# TinyNES_Main_Board.net
KiCad netlist of a schematic drawn in EAGLE
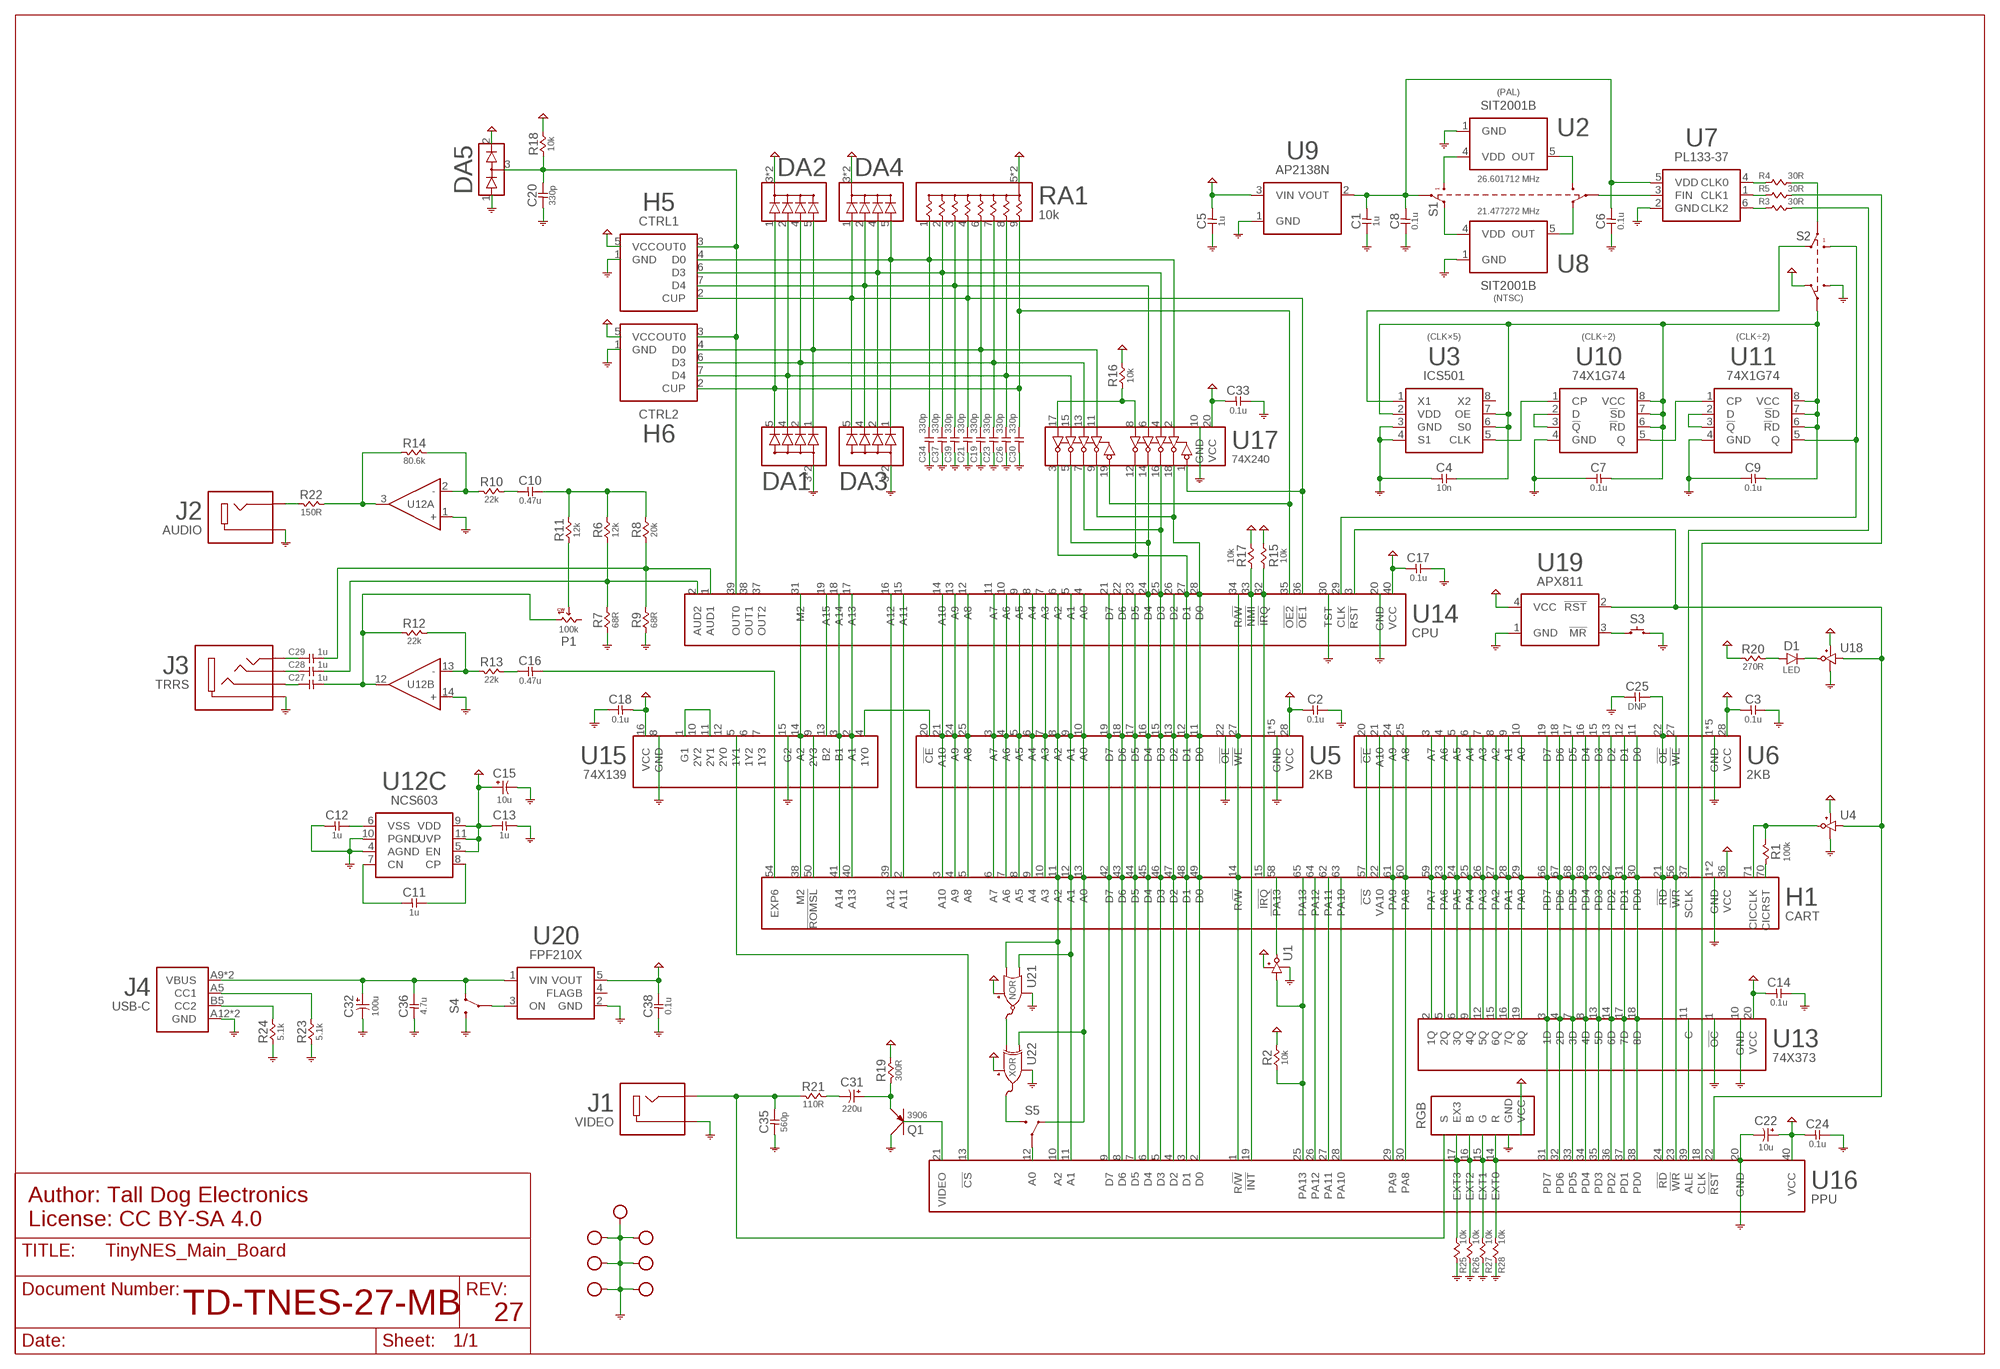
[diagram p0: schematic, sheet 1]

(export (version "E")
  (design (tool "Eeschema 10.0.6"))
  (components
    (comp (ref "C1")
      (value "1u")
      (footprint "eagle-import:0805-NP")
      (libsource (lib "eagle-import") (part "CAP-NP-0805"))
    )
    (comp (ref "C2")
      (value "0.1u")
      (footprint "eagle-import:0805-NP")
      (libsource (lib "eagle-import") (part "CAP-NP-0805"))
    )
    (comp (ref "C3")
      (value "0.1u")
      (footprint "eagle-import:0805-NP")
      (libsource (lib "eagle-import") (part "CAP-NP-0805"))
    )
    (comp (ref "C4")
      (value "10n")
      (footprint "eagle-import:0805-NP")
      (libsource (lib "eagle-import") (part "CAP-NP-0805"))
    )
    (comp (ref "C5")
      (value "1u")
      (footprint "eagle-import:0805-NP")
      (libsource (lib "eagle-import") (part "CAP-NP-0805"))
    )
    (comp (ref "C6")
      (value "0.1u")
      (footprint "eagle-import:0805-NP")
      (libsource (lib "eagle-import") (part "CAP-NP-0805"))
    )
    (comp (ref "C7")
      (value "0.1u")
      (footprint "eagle-import:0805-NP")
      (libsource (lib "eagle-import") (part "CAP-NP-0805"))
    )
    (comp (ref "C8")
      (value "0.1u")
      (footprint "eagle-import:0805-NP")
      (libsource (lib "eagle-import") (part "CAP-NP-0805"))
    )
    (comp (ref "C9")
      (value "0.1u")
      (footprint "eagle-import:0805-NP")
      (libsource (lib "eagle-import") (part "CAP-NP-0805"))
    )
    (comp (ref "C10")
      (value "0.47u")
      (footprint "eagle-import:1206-NP")
      (libsource (lib "eagle-import") (part "CAP-NP-1206"))
    )
    (comp (ref "C11")
      (value "1u")
      (footprint "eagle-import:0805-NP")
      (libsource (lib "eagle-import") (part "CAP-NP-0805"))
    )
    (comp (ref "C12")
      (value "1u")
      (footprint "eagle-import:0805-NP")
      (libsource (lib "eagle-import") (part "CAP-NP-0805"))
    )
    (comp (ref "C13")
      (value "1u")
      (footprint "eagle-import:0805-NP")
      (libsource (lib "eagle-import") (part "CAP-NP-0805"))
    )
    (comp (ref "C14")
      (value "0.1u")
      (footprint "eagle-import:0805-NP")
      (libsource (lib "eagle-import") (part "CAP-NP-0805"))
    )
    (comp (ref "C15")
      (value "10u")
      (footprint "eagle-import:ECAP-B")
      (libsource (lib "eagle-import") (part "CAP-P-B"))
    )
    (comp (ref "C16")
      (value "0.47u")
      (footprint "eagle-import:1206-NP")
      (libsource (lib "eagle-import") (part "CAP-NP-1206"))
    )
    (comp (ref "C17")
      (value "0.1u")
      (footprint "eagle-import:0805-NP")
      (libsource (lib "eagle-import") (part "CAP-NP-0805"))
    )
    (comp (ref "C18")
      (value "0.1u")
      (footprint "eagle-import:0805-NP")
      (libsource (lib "eagle-import") (part "CAP-NP-0805"))
    )
    (comp (ref "C19")
      (value "330p")
      (footprint "eagle-import:0805-NP")
      (libsource (lib "eagle-import") (part "CAP-NP-0805"))
    )
    (comp (ref "C20")
      (value "330p")
      (footprint "eagle-import:0805-NP")
      (libsource (lib "eagle-import") (part "CAP-NP-0805"))
    )
    (comp (ref "C21")
      (value "330p")
      (footprint "eagle-import:0805-NP")
      (libsource (lib "eagle-import") (part "CAP-NP-0805"))
    )
    (comp (ref "C22")
      (value "10u")
      (footprint "eagle-import:1206-P")
      (libsource (lib "eagle-import") (part "CAP-P-1206"))
    )
    (comp (ref "C23")
      (value "330p")
      (footprint "eagle-import:0805-NP")
      (libsource (lib "eagle-import") (part "CAP-NP-0805"))
    )
    (comp (ref "C24")
      (value "0.1u")
      (footprint "eagle-import:0805-NP")
      (libsource (lib "eagle-import") (part "CAP-NP-0805"))
    )
    (comp (ref "C25")
      (value "DNP")
      (footprint "eagle-import:0805-NP")
      (libsource (lib "eagle-import") (part "CAP-NP-0805"))
    )
    (comp (ref "C26")
      (value "330p")
      (footprint "eagle-import:0805-NP")
      (libsource (lib "eagle-import") (part "CAP-NP-0805"))
    )
    (comp (ref "C27")
      (value "1u")
      (footprint "eagle-import:1210-NP")
      (libsource (lib "eagle-import") (part "CAP-NP-1210"))
    )
    (comp (ref "C28")
      (value "1u")
      (footprint "eagle-import:1210-NP")
      (libsource (lib "eagle-import") (part "CAP-NP-1210"))
    )
    (comp (ref "C29")
      (value "1u")
      (footprint "eagle-import:1210-NP")
      (libsource (lib "eagle-import") (part "CAP-NP-1210"))
    )
    (comp (ref "C30")
      (value "330p")
      (footprint "eagle-import:0805-NP")
      (libsource (lib "eagle-import") (part "CAP-NP-0805"))
    )
    (comp (ref "C31")
      (value "220u")
      (footprint "eagle-import:ECAP-E")
      (libsource (lib "eagle-import") (part "CAP-P-E"))
    )
    (comp (ref "C32")
      (value "100u")
      (footprint "eagle-import:ECAP-D")
      (libsource (lib "eagle-import") (part "CAP-P-D"))
    )
    (comp (ref "C33")
      (value "0.1u")
      (footprint "eagle-import:0805-NP")
      (libsource (lib "eagle-import") (part "CAP-NP-0805"))
    )
    (comp (ref "C34")
      (value "330p")
      (footprint "eagle-import:0805-NP")
      (libsource (lib "eagle-import") (part "CAP-NP-0805"))
    )
    (comp (ref "C35")
      (value "560p")
      (footprint "eagle-import:0805-NP")
      (libsource (lib "eagle-import") (part "CAP-NP-0805"))
    )
    (comp (ref "C36")
      (value "4.7u")
      (footprint "eagle-import:0805-NP")
      (libsource (lib "eagle-import") (part "CAP-NP-0805"))
    )
    (comp (ref "C37")
      (value "330p")
      (footprint "eagle-import:0805-NP")
      (libsource (lib "eagle-import") (part "CAP-NP-0805"))
    )
    (comp (ref "C38")
      (value "0.1u")
      (footprint "eagle-import:0805-NP")
      (libsource (lib "eagle-import") (part "CAP-NP-0805"))
    )
    (comp (ref "C39")
      (value "330p")
      (footprint "eagle-import:0805-NP")
      (libsource (lib "eagle-import") (part "CAP-NP-0805"))
    )
    (comp (ref "D1")
      (value "LED")
      (footprint "eagle-import:LED-5MM")
      (libsource (lib "eagle-import") (part "DIODE-LED-5MM"))
    )
    (comp (ref "DA1")
      (value "DA4-CA-SOT-363")
      (footprint "eagle-import:SOT-363-NP")
      (libsource (lib "eagle-import") (part "DA4-CA-SOT-363"))
    )
    (comp (ref "DA2")
      (value "DA4-CK-SOT-363")
      (footprint "eagle-import:SOT-363-NP")
      (libsource (lib "eagle-import") (part "DA4-CK-SOT-363"))
    )
    (comp (ref "DA3")
      (value "DA4-CA-SOT-363")
      (footprint "eagle-import:SOT-363-NP")
      (libsource (lib "eagle-import") (part "DA4-CA-SOT-363"))
    )
    (comp (ref "DA4")
      (value "DA4-CK-SOT-363")
      (footprint "eagle-import:SOT-363-NP")
      (libsource (lib "eagle-import") (part "DA4-CK-SOT-363"))
    )
    (comp (ref "DA5")
      (value "DA2-S")
      (footprint "eagle-import:SOT-23-3")
      (libsource (lib "eagle-import") (part "DA2-S"))
    )
    (comp (ref "H1")
      (value "CART")
      (footprint "eagle-import:CART-72-2.50-CONN-VERT")
      (libsource (lib "eagle-import") (part "CART-72-CONN-VERT"))
    )
    (comp (ref "H5")
      (value "CTRL1")
      (footprint "eagle-import:JST-PH-7")
      (libsource (lib "eagle-import") (part "CTRL"))
    )
    (comp (ref "H6")
      (value "CTRL2")
      (footprint "eagle-import:JST-PH-7")
      (libsource (lib "eagle-import") (part "CTRL"))
    )
    (comp (ref "HOLE1")
      (value "HOLE-M2.5")
      (footprint "eagle-import:HOLE-M2.5")
      (libsource (lib "eagle-import") (part "HOLE-M2.5"))
    )
    (comp (ref "HOLE2")
      (value "HOLE-M2.5")
      (footprint "eagle-import:HOLE-M2.5")
      (libsource (lib "eagle-import") (part "HOLE-M2.5"))
    )
    (comp (ref "HOLE3")
      (value "HOLE-M2.5")
      (footprint "eagle-import:HOLE-M2.5")
      (libsource (lib "eagle-import") (part "HOLE-M2.5"))
    )
    (comp (ref "HOLE4")
      (value "HOLE-M2.5")
      (footprint "eagle-import:HOLE-M2.5")
      (libsource (lib "eagle-import") (part "HOLE-M2.5"))
    )
    (comp (ref "HOLE5")
      (value "HOLE-M2.5")
      (footprint "eagle-import:HOLE-M2.5")
      (libsource (lib "eagle-import") (part "HOLE-M2.5"))
    )
    (comp (ref "HOLE6")
      (value "HOLE-M2.5")
      (footprint "eagle-import:HOLE-M2.5")
      (libsource (lib "eagle-import") (part "HOLE-M2.5"))
    )
    (comp (ref "HOLE7")
      (value "HOLE-M2.5")
      (footprint "eagle-import:HOLE-M2.5")
      (libsource (lib "eagle-import") (part "HOLE-M2.5"))
    )
    (comp (ref "J1")
      (value "VIDEO")
      (footprint "eagle-import:RCJ")
      (libsource (lib "eagle-import") (part "JACK"))
    )
    (comp (ref "J2")
      (value "AUDIO")
      (footprint "eagle-import:RCJ")
      (libsource (lib "eagle-import") (part "JACK"))
    )
    (comp (ref "J3")
      (value "TRRS")
      (footprint "eagle-import:SJ-43514")
      (libsource (lib "eagle-import") (part "TRRS-SJ-43514"))
    )
    (comp (ref "J4")
      (value "USB-C")
      (footprint "eagle-import:USB4125")
      (libsource (lib "eagle-import") (part "USB-C-POWER"))
    )
    (comp (ref "P1")
      (value "100k")
      (footprint "eagle-import:POT-3361")
      (libsource (lib "eagle-import") (part "POT"))
    )
    (comp (ref "Q1")
      (value "3906")
      (footprint "eagle-import:SOT-23-3")
      (libsource (lib "eagle-import") (part "PNP"))
    )
    (comp (ref "R1")
      (value "100k")
      (footprint "eagle-import:0805-NP")
      (libsource (lib "eagle-import") (part "RESISTOR-0805"))
    )
    (comp (ref "R2")
      (value "10k")
      (footprint "eagle-import:0805-NP")
      (libsource (lib "eagle-import") (part "RESISTOR-0805"))
    )
    (comp (ref "R3")
      (value "30R")
      (footprint "eagle-import:0805-NP")
      (libsource (lib "eagle-import") (part "RESISTOR-0805"))
    )
    (comp (ref "R4")
      (value "30R")
      (footprint "eagle-import:0805-NP")
      (libsource (lib "eagle-import") (part "RESISTOR-0805"))
    )
    (comp (ref "R5")
      (value "30R")
      (footprint "eagle-import:0805-NP")
      (libsource (lib "eagle-import") (part "RESISTOR-0805"))
    )
    (comp (ref "R6")
      (value "12k")
      (footprint "eagle-import:0805-NP")
      (libsource (lib "eagle-import") (part "RESISTOR-0805"))
    )
    (comp (ref "R7")
      (value "68R")
      (footprint "eagle-import:0805-NP")
      (libsource (lib "eagle-import") (part "RESISTOR-0805"))
    )
    (comp (ref "R8")
      (value "20k")
      (footprint "eagle-import:0805-NP")
      (libsource (lib "eagle-import") (part "RESISTOR-0805"))
    )
    (comp (ref "R9")
      (value "68R")
      (footprint "eagle-import:0805-NP")
      (libsource (lib "eagle-import") (part "RESISTOR-0805"))
    )
    (comp (ref "R10")
      (value "22k")
      (footprint "eagle-import:0805-NP")
      (libsource (lib "eagle-import") (part "RESISTOR-0805"))
    )
    (comp (ref "R11")
      (value "12k")
      (footprint "eagle-import:0805-NP")
      (libsource (lib "eagle-import") (part "RESISTOR-0805"))
    )
    (comp (ref "R12")
      (value "22k")
      (footprint "eagle-import:0805-NP")
      (libsource (lib "eagle-import") (part "RESISTOR-0805"))
    )
    (comp (ref "R13")
      (value "22k")
      (footprint "eagle-import:0805-NP")
      (libsource (lib "eagle-import") (part "RESISTOR-0805"))
    )
    (comp (ref "R14")
      (value "80.6k")
      (footprint "eagle-import:0805-NP")
      (libsource (lib "eagle-import") (part "RESISTOR-0805"))
    )
    (comp (ref "R15")
      (value "10k")
      (footprint "eagle-import:0805-NP")
      (libsource (lib "eagle-import") (part "RESISTOR-0805"))
    )
    (comp (ref "R16")
      (value "10k")
      (footprint "eagle-import:0805-NP")
      (libsource (lib "eagle-import") (part "RESISTOR-0805"))
    )
    (comp (ref "R17")
      (value "10k")
      (footprint "eagle-import:0805-NP")
      (libsource (lib "eagle-import") (part "RESISTOR-0805"))
    )
    (comp (ref "R18")
      (value "10k")
      (footprint "eagle-import:0805-NP")
      (libsource (lib "eagle-import") (part "RESISTOR-0805"))
    )
    (comp (ref "R19")
      (value "300R")
      (footprint "eagle-import:0805-NP")
      (libsource (lib "eagle-import") (part "RESISTOR-0805"))
    )
    (comp (ref "R20")
      (value "270R")
      (footprint "eagle-import:0805-NP")
      (libsource (lib "eagle-import") (part "RESISTOR-0805"))
    )
    (comp (ref "R21")
      (value "110R")
      (footprint "eagle-import:0805-NP")
      (libsource (lib "eagle-import") (part "RESISTOR-0805"))
    )
    (comp (ref "R22")
      (value "150R")
      (footprint "eagle-import:0805-NP")
      (libsource (lib "eagle-import") (part "RESISTOR-0805"))
    )
    (comp (ref "R23")
      (value "5.1k")
      (footprint "eagle-import:0805-NP")
      (libsource (lib "eagle-import") (part "RESISTOR-0805"))
    )
    (comp (ref "R24")
      (value "5.1k")
      (footprint "eagle-import:0805-NP")
      (libsource (lib "eagle-import") (part "RESISTOR-0805"))
    )
    (comp (ref "R25")
      (value "10k")
      (footprint "eagle-import:0603-NP")
      (libsource (lib "eagle-import") (part "RESISTOR-0603"))
    )
    (comp (ref "R26")
      (value "10k")
      (footprint "eagle-import:0603-NP")
      (libsource (lib "eagle-import") (part "RESISTOR-0603"))
    )
    (comp (ref "R27")
      (value "10k")
      (footprint "eagle-import:0603-NP")
      (libsource (lib "eagle-import") (part "RESISTOR-0603"))
    )
    (comp (ref "R28")
      (value "10k")
      (footprint "eagle-import:0603-NP")
      (libsource (lib "eagle-import") (part "RESISTOR-0603"))
    )
    (comp (ref "RA1")
      (value "10k")
      (footprint "eagle-import:EXBA10P")
      (libsource (lib "eagle-import") (part "RA8"))
    )
    (comp (ref "RGB")
      (value "RGB-TOP")
      (footprint "eagle-import:RGB-TOP")
      (libsource (lib "eagle-import") (part "RGB-TOP"))
    )
    (comp (ref "S1")
      (value "DPDT-LONG")
      (footprint "eagle-import:JS202011J")
      (libsource (lib "eagle-import") (part "DPDT-LONG"))
    )
    (comp (ref "S2")
      (value "DPDT")
      (footprint "eagle-import:JS202011J")
      (libsource (lib "eagle-import") (part "DPDT"))
    )
    (comp (ref "S3")
      (value "SWITCH")
      (footprint "eagle-import:TL1105")
      (libsource (lib "eagle-import") (part "SWITCH"))
    )
    (comp (ref "S4")
      (value "SPDT-EG1213")
      (footprint "eagle-import:EG1213")
      (libsource (lib "eagle-import") (part "SPDT-EG1213"))
    )
    (comp (ref "S5")
      (value "SPDT-CUS-12TB")
      (footprint "eagle-import:CUS-12TB")
      (libsource (lib "eagle-import") (part "SPDT-CUS-12TB"))
    )
    (comp (ref "U1")
      (value "BUFFER")
      (footprint "eagle-import:SOT-23-5")
      (libsource (lib "eagle-import") (part "BUFFER"))
    )
    (comp (ref "U2")
      (value "SIT2001B")
      (footprint "eagle-import:SOT-23-5")
      (libsource (lib "eagle-import") (part "SIT2001B"))
    )
    (comp (ref "U3")
      (value "ICS501")
      (footprint "eagle-import:SOIC-8")
      (libsource (lib "eagle-import") (part "ICS501"))
    )
    (comp (ref "U4")
      (value "BUFFER")
      (footprint "eagle-import:SOT-23-5")
      (libsource (lib "eagle-import") (part "BUFFER"))
    )
    (comp (ref "U5")
      (value "2KB")
      (footprint "eagle-import:SOIC-28")
      (libsource (lib "eagle-import") (part "2KB"))
    )
    (comp (ref "U6")
      (value "2KB")
      (footprint "eagle-import:SOIC-28")
      (libsource (lib "eagle-import") (part "2KB"))
    )
    (comp (ref "U7")
      (value "PL133-37")
      (footprint "eagle-import:SOT-23-6")
      (libsource (lib "eagle-import") (part "PL133-37"))
    )
    (comp (ref "U8")
      (value "SIT2001B")
      (footprint "eagle-import:SOT-23-5")
      (libsource (lib "eagle-import") (part "SIT2001B"))
    )
    (comp (ref "U9")
      (value "AP2138N")
      (footprint "eagle-import:SOT-23-3")
      (libsource (lib "eagle-import") (part "AP2138N"))
    )
    (comp (ref "U10")
      (value "74X1G74")
      (footprint "eagle-import:TSSOP-8")
      (libsource (lib "eagle-import") (part "74X1G74"))
    )
    (comp (ref "U11")
      (value "74X1G74")
      (footprint "eagle-import:TSSOP-8")
      (libsource (lib "eagle-import") (part "74X1G74"))
    )
    (comp (ref "U12")
      (value "NCS603")
      (footprint "eagle-import:TSSOP-14")
      (libsource (lib "eagle-import") (part "NCS603"))
    )
    (comp (ref "U13")
      (value "74X373")
      (footprint "eagle-import:SOIC-20")
      (libsource (lib "eagle-import") (part "74X373"))
    )
    (comp (ref "U14")
      (value "CPU")
      (footprint "eagle-import:DIP-40")
      (libsource (lib "eagle-import") (part "CPU"))
    )
    (comp (ref "U15")
      (value "74X139")
      (footprint "eagle-import:SOIC-16")
      (libsource (lib "eagle-import") (part "74X139"))
    )
    (comp (ref "U16")
      (value "PPU")
      (footprint "eagle-import:DIP-40")
      (libsource (lib "eagle-import") (part "PPU"))
    )
    (comp (ref "U17")
      (value "74X240")
      (footprint "eagle-import:SOIC-20")
      (libsource (lib "eagle-import") (part "74X240"))
    )
    (comp (ref "U18")
      (value "BUFFER")
      (footprint "eagle-import:SOT-23-5")
      (libsource (lib "eagle-import") (part "BUFFER"))
    )
    (comp (ref "U19")
      (value "APX811")
      (footprint "eagle-import:SOT-143")
      (libsource (lib "eagle-import") (part "APX811"))
    )
    (comp (ref "U20")
      (value "FPF210X")
      (footprint "eagle-import:SOT-23-5")
      (libsource (lib "eagle-import") (part "FPF210X"))
    )
    (comp (ref "U21")
      (value "NOR")
      (footprint "eagle-import:SOT-23-5")
      (libsource (lib "eagle-import") (part "NOR"))
    )
    (comp (ref "U22")
      (value "XOR")
      (footprint "eagle-import:SOT-23-5")
      (libsource (lib "eagle-import") (part "XOR"))
    )
  )
  (nets
    (net (code "1") (name "GND") (class "Default")
      (node (ref "C1") (pin "2") (pinfunction "2_2") (pintype "bidirectional"))
      (node (ref "C12") (pin "1") (pinfunction "1_1") (pintype "bidirectional"))
      (node (ref "C13") (pin "1") (pinfunction "1_1") (pintype "bidirectional"))
      (node (ref "C14") (pin "2") (pinfunction "2_2") (pintype "bidirectional"))
      (node (ref "C15") (pin "C") (pinfunction "C_C") (pintype "bidirectional"))
      (node (ref "C17") (pin "2") (pinfunction "2_2") (pintype "bidirectional"))
      (node (ref "C18") (pin "2") (pinfunction "2_2") (pintype "bidirectional"))
      (node (ref "C19") (pin "1") (pinfunction "1_1") (pintype "bidirectional"))
      (node (ref "C2") (pin "2") (pinfunction "2_2") (pintype "bidirectional"))
      (node (ref "C20") (pin "1") (pinfunction "1_1") (pintype "bidirectional"))
      (node (ref "C21") (pin "1") (pinfunction "1_1") (pintype "bidirectional"))
      (node (ref "C22") (pin "N") (pinfunction "C_N") (pintype "bidirectional"))
      (node (ref "C23") (pin "1") (pinfunction "1_1") (pintype "bidirectional"))
      (node (ref "C24") (pin "2") (pinfunction "2_2") (pintype "bidirectional"))
      (node (ref "C25") (pin "1") (pinfunction "1_1") (pintype "bidirectional"))
      (node (ref "C26") (pin "1") (pinfunction "1_1") (pintype "bidirectional"))
      (node (ref "C3") (pin "2") (pinfunction "2_2") (pintype "bidirectional"))
      (node (ref "C30") (pin "1") (pinfunction "1_1") (pintype "bidirectional"))
      (node (ref "C32") (pin "C") (pinfunction "C_C") (pintype "bidirectional"))
      (node (ref "C33") (pin "2") (pinfunction "2_2") (pintype "bidirectional"))
      (node (ref "C34") (pin "1") (pinfunction "1_1") (pintype "bidirectional"))
      (node (ref "C35") (pin "1") (pinfunction "1_1") (pintype "bidirectional"))
      (node (ref "C36") (pin "1") (pinfunction "1_1") (pintype "bidirectional"))
      (node (ref "C37") (pin "1") (pinfunction "1_1") (pintype "bidirectional"))
      (node (ref "C38") (pin "1") (pinfunction "1_1") (pintype "bidirectional"))
      (node (ref "C39") (pin "1") (pinfunction "1_1") (pintype "bidirectional"))
      (node (ref "C4") (pin "1") (pinfunction "1_1") (pintype "bidirectional"))
      (node (ref "C5") (pin "2") (pinfunction "2_2") (pintype "bidirectional"))
      (node (ref "C6") (pin "2") (pinfunction "2_2") (pintype "bidirectional"))
      (node (ref "C7") (pin "2") (pinfunction "2_2") (pintype "bidirectional"))
      (node (ref "C8") (pin "2") (pinfunction "2_2") (pintype "bidirectional"))
      (node (ref "C9") (pin "2") (pinfunction "2_2") (pintype "bidirectional"))
      (node (ref "DA1") (pin "3") (pinfunction "COM_3") (pintype "bidirectional"))
      (node (ref "DA1") (pin "6") (pinfunction "COM_6") (pintype "bidirectional"))
      (node (ref "DA3") (pin "3") (pinfunction "COM_3") (pintype "bidirectional"))
      (node (ref "DA3") (pin "6") (pinfunction "COM_6") (pintype "bidirectional"))
      (node (ref "DA5") (pin "1") (pinfunction "A_1") (pintype "bidirectional"))
      (node (ref "H1") (pin "1") (pinfunction "GND_1") (pintype "bidirectional"))
      (node (ref "H1") (pin "72") (pinfunction "GND_72") (pintype "bidirectional"))
      (node (ref "H5") (pin "1") (pinfunction "GND_1") (pintype "bidirectional"))
      (node (ref "H6") (pin "1") (pinfunction "GND_1") (pintype "bidirectional"))
      (node (ref "HOLE1") (pin "P$1") (pinfunction "P$1_P$1") (pintype "bidirectional"))
      (node (ref "HOLE1") (pin "P$13") (pinfunction "P$1_P$13") (pintype "bidirectional"))
      (node (ref "HOLE1") (pin "P$14") (pinfunction "P$1_P$14") (pintype "bidirectional"))
      (node (ref "HOLE1") (pin "P$15") (pinfunction "P$1_P$15") (pintype "bidirectional"))
      (node (ref "HOLE1") (pin "P$16") (pinfunction "P$1_P$16") (pintype "bidirectional"))
      (node (ref "HOLE1") (pin "P$6") (pinfunction "P$1_P$6") (pintype "bidirectional"))
      (node (ref "HOLE1") (pin "P$7") (pinfunction "P$1_P$7") (pintype "bidirectional"))
      (node (ref "HOLE1") (pin "P$8") (pinfunction "P$1_P$8") (pintype "bidirectional"))
      (node (ref "HOLE1") (pin "P$9") (pinfunction "P$1_P$9") (pintype "bidirectional"))
      (node (ref "HOLE2") (pin "P$1") (pinfunction "P$1_P$1") (pintype "bidirectional"))
      (node (ref "HOLE2") (pin "P$13") (pinfunction "P$1_P$13") (pintype "bidirectional"))
      (node (ref "HOLE2") (pin "P$14") (pinfunction "P$1_P$14") (pintype "bidirectional"))
      (node (ref "HOLE2") (pin "P$15") (pinfunction "P$1_P$15") (pintype "bidirectional"))
      (node (ref "HOLE2") (pin "P$16") (pinfunction "P$1_P$16") (pintype "bidirectional"))
      (node (ref "HOLE2") (pin "P$6") (pinfunction "P$1_P$6") (pintype "bidirectional"))
      (node (ref "HOLE2") (pin "P$7") (pinfunction "P$1_P$7") (pintype "bidirectional"))
      (node (ref "HOLE2") (pin "P$8") (pinfunction "P$1_P$8") (pintype "bidirectional"))
      (node (ref "HOLE2") (pin "P$9") (pinfunction "P$1_P$9") (pintype "bidirectional"))
      (node (ref "HOLE3") (pin "P$1") (pinfunction "P$1_P$1") (pintype "bidirectional"))
      (node (ref "HOLE3") (pin "P$13") (pinfunction "P$1_P$13") (pintype "bidirectional"))
      (node (ref "HOLE3") (pin "P$14") (pinfunction "P$1_P$14") (pintype "bidirectional"))
      (node (ref "HOLE3") (pin "P$15") (pinfunction "P$1_P$15") (pintype "bidirectional"))
      (node (ref "HOLE3") (pin "P$16") (pinfunction "P$1_P$16") (pintype "bidirectional"))
      (node (ref "HOLE3") (pin "P$6") (pinfunction "P$1_P$6") (pintype "bidirectional"))
      (node (ref "HOLE3") (pin "P$7") (pinfunction "P$1_P$7") (pintype "bidirectional"))
      (node (ref "HOLE3") (pin "P$8") (pinfunction "P$1_P$8") (pintype "bidirectional"))
      (node (ref "HOLE3") (pin "P$9") (pinfunction "P$1_P$9") (pintype "bidirectional"))
      (node (ref "HOLE4") (pin "P$1") (pinfunction "P$1_P$1") (pintype "bidirectional"))
      (node (ref "HOLE4") (pin "P$13") (pinfunction "P$1_P$13") (pintype "bidirectional"))
      (node (ref "HOLE4") (pin "P$14") (pinfunction "P$1_P$14") (pintype "bidirectional"))
      (node (ref "HOLE4") (pin "P$15") (pinfunction "P$1_P$15") (pintype "bidirectional"))
      (node (ref "HOLE4") (pin "P$16") (pinfunction "P$1_P$16") (pintype "bidirectional"))
      (node (ref "HOLE4") (pin "P$6") (pinfunction "P$1_P$6") (pintype "bidirectional"))
      (node (ref "HOLE4") (pin "P$7") (pinfunction "P$1_P$7") (pintype "bidirectional"))
      (node (ref "HOLE4") (pin "P$8") (pinfunction "P$1_P$8") (pintype "bidirectional"))
      (node (ref "HOLE4") (pin "P$9") (pinfunction "P$1_P$9") (pintype "bidirectional"))
      (node (ref "HOLE5") (pin "P$1") (pinfunction "P$1_P$1") (pintype "bidirectional"))
      (node (ref "HOLE5") (pin "P$13") (pinfunction "P$1_P$13") (pintype "bidirectional"))
      (node (ref "HOLE5") (pin "P$14") (pinfunction "P$1_P$14") (pintype "bidirectional"))
      (node (ref "HOLE5") (pin "P$15") (pinfunction "P$1_P$15") (pintype "bidirectional"))
      (node (ref "HOLE5") (pin "P$16") (pinfunction "P$1_P$16") (pintype "bidirectional"))
      (node (ref "HOLE5") (pin "P$6") (pinfunction "P$1_P$6") (pintype "bidirectional"))
      (node (ref "HOLE5") (pin "P$7") (pinfunction "P$1_P$7") (pintype "bidirectional"))
      (node (ref "HOLE5") (pin "P$8") (pinfunction "P$1_P$8") (pintype "bidirectional"))
      (node (ref "HOLE5") (pin "P$9") (pinfunction "P$1_P$9") (pintype "bidirectional"))
      (node (ref "HOLE6") (pin "P$1") (pinfunction "P$1_P$1") (pintype "bidirectional"))
      (node (ref "HOLE6") (pin "P$13") (pinfunction "P$1_P$13") (pintype "bidirectional"))
      (node (ref "HOLE6") (pin "P$14") (pinfunction "P$1_P$14") (pintype "bidirectional"))
      (node (ref "HOLE6") (pin "P$15") (pinfunction "P$1_P$15") (pintype "bidirectional"))
      (node (ref "HOLE6") (pin "P$16") (pinfunction "P$1_P$16") (pintype "bidirectional"))
      (node (ref "HOLE6") (pin "P$6") (pinfunction "P$1_P$6") (pintype "bidirectional"))
      (node (ref "HOLE6") (pin "P$7") (pinfunction "P$1_P$7") (pintype "bidirectional"))
      (node (ref "HOLE6") (pin "P$8") (pinfunction "P$1_P$8") (pintype "bidirectional"))
      (node (ref "HOLE6") (pin "P$9") (pinfunction "P$1_P$9") (pintype "bidirectional"))
      (node (ref "HOLE7") (pin "P$1") (pinfunction "P$1_P$1") (pintype "bidirectional"))
      (node (ref "HOLE7") (pin "P$13") (pinfunction "P$1_P$13") (pintype "bidirectional"))
      (node (ref "HOLE7") (pin "P$14") (pinfunction "P$1_P$14") (pintype "bidirectional"))
      (node (ref "HOLE7") (pin "P$15") (pinfunction "P$1_P$15") (pintype "bidirectional"))
      (node (ref "HOLE7") (pin "P$16") (pinfunction "P$1_P$16") (pintype "bidirectional"))
      (node (ref "HOLE7") (pin "P$6") (pinfunction "P$1_P$6") (pintype "bidirectional"))
      (node (ref "HOLE7") (pin "P$7") (pinfunction "P$1_P$7") (pintype "bidirectional"))
      (node (ref "HOLE7") (pin "P$8") (pinfunction "P$1_P$8") (pintype "bidirectional"))
      (node (ref "HOLE7") (pin "P$9") (pinfunction "P$1_P$9") (pintype "bidirectional"))
      (node (ref "J1") (pin "1B") (pinfunction "S_1B") (pintype "bidirectional"))
      (node (ref "J1") (pin "1T") (pinfunction "S_1T") (pintype "bidirectional"))
      (node (ref "J2") (pin "1B") (pinfunction "S_1B") (pintype "bidirectional"))
      (node (ref "J2") (pin "1T") (pinfunction "S_1T") (pintype "bidirectional"))
      (node (ref "J3") (pin "1") (pinfunction "S_1") (pintype "bidirectional"))
      (node (ref "J4") (pin "A12") (pinfunction "GND_A12") (pintype "bidirectional"))
      (node (ref "J4") (pin "B12") (pinfunction "GND_B12") (pintype "bidirectional"))
      (node (ref "Q1") (pin "3") (pinfunction "C_3") (pintype "bidirectional"))
      (node (ref "R23") (pin "1") (pinfunction "1_1") (pintype "bidirectional"))
      (node (ref "R24") (pin "1") (pinfunction "1_1") (pintype "bidirectional"))
      (node (ref "R25") (pin "1") (pinfunction "1_1") (pintype "bidirectional"))
      (node (ref "R26") (pin "1") (pinfunction "1_1") (pintype "bidirectional"))
      (node (ref "R27") (pin "1") (pinfunction "1_1") (pintype "bidirectional"))
      (node (ref "R28") (pin "1") (pinfunction "1_1") (pintype "bidirectional"))
      (node (ref "R7") (pin "1") (pinfunction "1_1") (pintype "bidirectional"))
      (node (ref "R9") (pin "1") (pinfunction "1_1") (pintype "bidirectional"))
      (node (ref "RGB") (pin "GND") (pinfunction "GND_GND") (pintype "bidirectional"))
      (node (ref "S2") (pin "AA") (pinfunction "4_AA") (pintype "bidirectional"))
      (node (ref "S3") (pin "2") (pinfunction "2_2") (pintype "bidirectional"))
      (node (ref "S4") (pin "3") (pinfunction "3_3") (pintype "bidirectional"))
      (node (ref "U1") (pin "1") (pinfunction "GND_1") (pintype "bidirectional"))
      (node (ref "U1") (pin "3") (pinfunction "GND_3") (pintype "bidirectional"))
      (node (ref "U10") (pin "4") (pinfunction "GND_4") (pintype "bidirectional"))
      (node (ref "U11") (pin "4") (pinfunction "GND_4") (pintype "bidirectional"))
      (node (ref "U12") (pin "1") (pinfunction "+_1") (pintype "input"))
      (node (ref "U12") (pin "10") (pinfunction "PGND_10") (pintype "bidirectional"))
      (node (ref "U12") (pin "14") (pinfunction "+_14") (pintype "input"))
      (node (ref "U12") (pin "4") (pinfunction "AGND_4") (pintype "bidirectional"))
      (node (ref "U13") (pin "1") (pinfunction "~{OC}_1") (pintype "bidirectional"))
      (node (ref "U13") (pin "10") (pinfunction "GND_10") (pintype "bidirectional"))
      (node (ref "U14") (pin "20") (pinfunction "GND_20") (pintype "bidirectional"))
      (node (ref "U14") (pin "30") (pinfunction "TST_30") (pintype "bidirectional"))
      (node (ref "U15") (pin "15") (pinfunction "G2_15") (pintype "bidirectional"))
      (node (ref "U15") (pin "8") (pinfunction "GND_8") (pintype "bidirectional"))
      (node (ref "U16") (pin "20") (pinfunction "GND_20") (pintype "bidirectional"))
      (node (ref "U17") (pin "10") (pinfunction "GND_10") (pintype "bidirectional"))
      (node (ref "U18") (pin "1") (pinfunction "GND_1") (pintype "bidirectional"))
      (node (ref "U18") (pin "3") (pinfunction "GND_3") (pintype "bidirectional"))
      (node (ref "U19") (pin "1") (pinfunction "GND_1") (pintype "bidirectional"))
      (node (ref "U2") (pin "1") (pinfunction "GND_1") (pintype "bidirectional"))
      (node (ref "U20") (pin "2") (pinfunction "GND_2") (pintype "bidirectional"))
      (node (ref "U21") (pin "3") (pinfunction "GND_3") (pintype "power_in"))
      (node (ref "U22") (pin "3") (pinfunction "GND_3") (pintype "power_in"))
      (node (ref "U3") (pin "3") (pinfunction "GND_3") (pintype "bidirectional"))
      (node (ref "U3") (pin "4") (pinfunction "S1_4") (pintype "bidirectional"))
      (node (ref "U4") (pin "1") (pinfunction "GND_1") (pintype "bidirectional"))
      (node (ref "U4") (pin "3") (pinfunction "GND_3") (pintype "bidirectional"))
      (node (ref "U5") (pin "1") (pinfunction "GND_1") (pintype "bidirectional"))
      (node (ref "U5") (pin "14") (pinfunction "GND_14") (pintype "bidirectional"))
      (node (ref "U5") (pin "2") (pinfunction "GND_2") (pintype "bidirectional"))
      (node (ref "U5") (pin "22") (pinfunction "~{OE}_22") (pintype "bidirectional"))
      (node (ref "U5") (pin "23") (pinfunction "GND_23") (pintype "bidirectional"))
      (node (ref "U5") (pin "26") (pinfunction "GND_26") (pintype "bidirectional"))
      (node (ref "U6") (pin "1") (pinfunction "GND_1") (pintype "bidirectional"))
      (node (ref "U6") (pin "14") (pinfunction "GND_14") (pintype "bidirectional"))
      (node (ref "U6") (pin "2") (pinfunction "GND_2") (pintype "bidirectional"))
      (node (ref "U6") (pin "23") (pinfunction "GND_23") (pintype "bidirectional"))
      (node (ref "U6") (pin "26") (pinfunction "GND_26") (pintype "bidirectional"))
      (node (ref "U7") (pin "2") (pinfunction "GND_2") (pintype "bidirectional"))
      (node (ref "U8") (pin "1") (pinfunction "GND_1") (pintype "bidirectional"))
      (node (ref "U9") (pin "1") (pinfunction "GND_1") (pintype "bidirectional"))
    )
    (net (code "2") (name "Net-(C10-Pad1)") (class "Default")
      (node (ref "C10") (pin "1") (pinfunction "1_1") (pintype "bidirectional"))
      (node (ref "R10") (pin "1") (pinfunction "1_1") (pintype "bidirectional"))
    )
    (net (code "3") (name "Net-(C10-Pad2)") (class "Default")
      (node (ref "C10") (pin "2") (pinfunction "2_2") (pintype "bidirectional"))
      (node (ref "R11") (pin "2") (pinfunction "2_2") (pintype "bidirectional"))
      (node (ref "R6") (pin "2") (pinfunction "2_2") (pintype "bidirectional"))
      (node (ref "R8") (pin "2") (pinfunction "2_2") (pintype "bidirectional"))
    )
    (net (code "4") (name "Net-(C16-Pad2)") (class "Default")
      (node (ref "C16") (pin "2") (pinfunction "2_2") (pintype "bidirectional"))
      (node (ref "R13") (pin "1") (pinfunction "1_1") (pintype "bidirectional"))
    )
    (net (code "5") (name "Net-(C31-PadC)") (class "Default")
      (node (ref "C31") (pin "C") (pinfunction "C_C") (pintype "bidirectional"))
      (node (ref "R21") (pin "1") (pinfunction "1_1") (pintype "bidirectional"))
    )
    (net (code "6") (name "Net-(C35-Pad2)") (class "Default")
      (node (ref "C35") (pin "2") (pinfunction "2_2") (pintype "bidirectional"))
      (node (ref "J1") (pin "2B") (pinfunction "T_2B") (pintype "bidirectional"))
      (node (ref "J1") (pin "2T") (pinfunction "T_2T") (pintype "bidirectional"))
      (node (ref "R21") (pin "2") (pinfunction "2_2") (pintype "bidirectional"))
      (node (ref "RGB") (pin "S") (pinfunction "S_S") (pintype "bidirectional"))
    )
    (net (code "7") (name "Net-(D1-C)") (class "Default")
      (node (ref "D1") (pin "K") (pinfunction "C_K") (pintype "bidirectional"))
      (node (ref "U18") (pin "4") (pinfunction "Y_4") (pintype "bidirectional"))
    )
    (net (code "8") (name "Net-(D1-PadA)") (class "Default")
      (node (ref "D1") (pin "A") (pinfunction "A_A") (pintype "bidirectional"))
      (node (ref "R20") (pin "1") (pinfunction "1_1") (pintype "bidirectional"))
    )
    (net (code "9") (name "Net-(DA1-3)") (class "Default")
      (node (ref "C26") (pin "2") (pinfunction "2_2") (pintype "bidirectional"))
      (node (ref "DA1") (pin "4") (pinfunction "3_4") (pintype "bidirectional"))
      (node (ref "DA2") (pin "2") (pinfunction "2_2") (pintype "bidirectional"))
      (node (ref "H6") (pin "7") (pinfunction "D4_7") (pintype "bidirectional"))
      (node (ref "RA1") (pin "8") (pinfunction "7_8") (pintype "bidirectional"))
      (node (ref "U17") (pin "15") (pinfunction "2A3_15") (pintype "bidirectional"))
    )
    (net (code "10") (name "Net-(DA1-4)") (class "Default")
      (node (ref "C30") (pin "2") (pinfunction "2_2") (pintype "bidirectional"))
      (node (ref "DA1") (pin "5") (pinfunction "4_5") (pintype "bidirectional"))
      (node (ref "DA2") (pin "1") (pinfunction "1_1") (pintype "bidirectional"))
      (node (ref "H6") (pin "2") (pinfunction "CUP_2") (pintype "bidirectional"))
      (node (ref "RA1") (pin "9") (pinfunction "8_9") (pintype "bidirectional"))
      (node (ref "U14") (pin "35") (pinfunction "~{OE2}_35") (pintype "bidirectional"))
      (node (ref "U17") (pin "19") (pinfunction "2~{OE}_19") (pintype "bidirectional"))
    )
    (net (code "11") (name "Net-(DA2-3)") (class "Default")
      (node (ref "C23") (pin "2") (pinfunction "2_2") (pintype "bidirectional"))
      (node (ref "DA1") (pin "2") (pinfunction "2_2") (pintype "bidirectional"))
      (node (ref "DA2") (pin "4") (pinfunction "3_4") (pintype "bidirectional"))
      (node (ref "H6") (pin "6") (pinfunction "D3_6") (pintype "bidirectional"))
      (node (ref "RA1") (pin "7") (pinfunction "6_7") (pintype "bidirectional"))
      (node (ref "U17") (pin "13") (pinfunction "2A2_13") (pintype "bidirectional"))
    )
    (net (code "12") (name "Net-(DA2-4)") (class "Default")
      (node (ref "C19") (pin "2") (pinfunction "2_2") (pintype "bidirectional"))
      (node (ref "DA1") (pin "1") (pinfunction "1_1") (pintype "bidirectional"))
      (node (ref "DA2") (pin "5") (pinfunction "4_5") (pintype "bidirectional"))
      (node (ref "H6") (pin "4") (pinfunction "D0_4") (pintype "bidirectional"))
      (node (ref "RA1") (pin "6") (pinfunction "5_6") (pintype "bidirectional"))
      (node (ref "U17") (pin "11") (pinfunction "2A1_11") (pintype "bidirectional"))
    )
    (net (code "13") (name "Net-(DA3-3)") (class "Default")
      (node (ref "C39") (pin "2") (pinfunction "2_2") (pintype "bidirectional"))
      (node (ref "DA3") (pin "4") (pinfunction "3_4") (pintype "bidirectional"))
      (node (ref "DA4") (pin "2") (pinfunction "2_2") (pintype "bidirectional"))
      (node (ref "H5") (pin "7") (pinfunction "D4_7") (pintype "bidirectional"))
      (node (ref "RA1") (pin "3") (pinfunction "3_3") (pintype "bidirectional"))
      (node (ref "U17") (pin "6") (pinfunction "1A3_6") (pintype "bidirectional"))
    )
    (net (code "14") (name "Net-(DA3-4)") (class "Default")
      (node (ref "C21") (pin "2") (pinfunction "2_2") (pintype "bidirectional"))
      (node (ref "DA3") (pin "5") (pinfunction "4_5") (pintype "bidirectional"))
      (node (ref "DA4") (pin "1") (pinfunction "1_1") (pintype "bidirectional"))
      (node (ref "H5") (pin "2") (pinfunction "CUP_2") (pintype "bidirectional"))
      (node (ref "RA1") (pin "4") (pinfunction "4_4") (pintype "bidirectional"))
      (node (ref "U14") (pin "36") (pinfunction "~{OE1}_36") (pintype "bidirectional"))
      (node (ref "U17") (pin "1") (pinfunction "1~{OE}_1") (pintype "bidirectional"))
    )
    (net (code "15") (name "Net-(DA4-3)") (class "Default")
      (node (ref "C37") (pin "2") (pinfunction "2_2") (pintype "bidirectional"))
      (node (ref "DA3") (pin "2") (pinfunction "2_2") (pintype "bidirectional"))
      (node (ref "DA4") (pin "4") (pinfunction "3_4") (pintype "bidirectional"))
      (node (ref "H5") (pin "6") (pinfunction "D3_6") (pintype "bidirectional"))
      (node (ref "RA1") (pin "2") (pinfunction "2_2") (pintype "bidirectional"))
      (node (ref "U17") (pin "4") (pinfunction "1A2_4") (pintype "bidirectional"))
    )
    (net (code "16") (name "Net-(DA4-4)") (class "Default")
      (node (ref "C34") (pin "2") (pinfunction "2_2") (pintype "bidirectional"))
      (node (ref "DA3") (pin "1") (pinfunction "1_1") (pintype "bidirectional"))
      (node (ref "DA4") (pin "5") (pinfunction "4_5") (pintype "bidirectional"))
      (node (ref "H5") (pin "4") (pinfunction "D0_4") (pintype "bidirectional"))
      (node (ref "RA1") (pin "1") (pinfunction "1_1") (pintype "bidirectional"))
      (node (ref "U17") (pin "2") (pinfunction "1A1_2") (pintype "bidirectional"))
    )
    (net (code "17") (name "Net-(DA5-COM)") (class "Default")
      (node (ref "C20") (pin "2") (pinfunction "2_2") (pintype "bidirectional"))
      (node (ref "DA5") (pin "3") (pinfunction "COM_3") (pintype "bidirectional"))
      (node (ref "H5") (pin "3") (pinfunction "OUT0_3") (pintype "bidirectional"))
      (node (ref "H6") (pin "3") (pinfunction "OUT0_3") (pintype "bidirectional"))
      (node (ref "R18") (pin "1") (pinfunction "1_1") (pintype "bidirectional"))
      (node (ref "U14") (pin "39") (pinfunction "OUT0_39") (pintype "bidirectional"))
    )
    (net (code "18") (name "Net-(H1-A0)") (class "Default")
      (node (ref "H1") (pin "13") (pinfunction "A0_13") (pintype "bidirectional"))
      (node (ref "S5") (pin "1") (pinfunction "1_1") (pintype "bidirectional"))
      (node (ref "U14") (pin "4") (pinfunction "A0_4") (pintype "bidirectional"))
      (node (ref "U22") (pin "1") (pinfunction "B_1") (pintype "input"))
      (node (ref "U5") (pin "10") (pinfunction "A0_10") (pintype "bidirectional"))
    )
    (net (code "19") (name "Net-(H1-A1)") (class "Default")
      (node (ref "H1") (pin "12") (pinfunction "A1_12") (pintype "bidirectional"))
      (node (ref "U14") (pin "5") (pinfunction "A1_5") (pintype "bidirectional"))
      (node (ref "U16") (pin "11") (pinfunction "A1_11") (pintype "bidirectional"))
      (node (ref "U21") (pin "1") (pinfunction "B_1") (pintype "input"))
      (node (ref "U5") (pin "9") (pinfunction "A1_9") (pintype "bidirectional"))
    )
    (net (code "20") (name "Net-(H1-A2)") (class "Default")
      (node (ref "H1") (pin "11") (pinfunction "A2_11") (pintype "bidirectional"))
      (node (ref "U14") (pin "6") (pinfunction "A2_6") (pintype "bidirectional"))
      (node (ref "U16") (pin "10") (pinfunction "A2_10") (pintype "bidirectional"))
      (node (ref "U21") (pin "2") (pinfunction "A_2") (pintype "input"))
      (node (ref "U5") (pin "8") (pinfunction "A2_8") (pintype "bidirectional"))
    )
    (net (code "21") (name "Net-(H1-A3)") (class "Default")
      (node (ref "H1") (pin "10") (pinfunction "A3_10") (pintype "bidirectional"))
      (node (ref "U14") (pin "7") (pinfunction "A3_7") (pintype "bidirectional"))
      (node (ref "U5") (pin "7") (pinfunction "A3_7") (pintype "bidirectional"))
    )
    (net (code "22") (name "Net-(H1-A4)") (class "Default")
      (node (ref "H1") (pin "9") (pinfunction "A4_9") (pintype "bidirectional"))
      (node (ref "U14") (pin "8") (pinfunction "A4_8") (pintype "bidirectional"))
      (node (ref "U5") (pin "6") (pinfunction "A4_6") (pintype "bidirectional"))
    )
    (net (code "23") (name "Net-(H1-A5)") (class "Default")
      (node (ref "H1") (pin "8") (pinfunction "A5_8") (pintype "bidirectional"))
      (node (ref "U14") (pin "9") (pinfunction "A5_9") (pintype "bidirectional"))
      (node (ref "U5") (pin "5") (pinfunction "A5_5") (pintype "bidirectional"))
    )
    (net (code "24") (name "Net-(H1-A6)") (class "Default")
      (node (ref "H1") (pin "7") (pinfunction "A6_7") (pintype "bidirectional"))
      (node (ref "U14") (pin "10") (pinfunction "A6_10") (pintype "bidirectional"))
      (node (ref "U5") (pin "4") (pinfunction "A6_4") (pintype "bidirectional"))
    )
    (net (code "25") (name "Net-(H1-A7)") (class "Default")
      (node (ref "H1") (pin "6") (pinfunction "A7_6") (pintype "bidirectional"))
      (node (ref "U14") (pin "11") (pinfunction "A7_11") (pintype "bidirectional"))
      (node (ref "U5") (pin "3") (pinfunction "A7_3") (pintype "bidirectional"))
    )
    (net (code "26") (name "Net-(H1-A8)") (class "Default")
      (node (ref "H1") (pin "5") (pinfunction "A8_5") (pintype "bidirectional"))
      (node (ref "U14") (pin "12") (pinfunction "A8_12") (pintype "bidirectional"))
      (node (ref "U5") (pin "25") (pinfunction "A8_25") (pintype "bidirectional"))
    )
    (net (code "27") (name "Net-(H1-A9)") (class "Default")
      (node (ref "H1") (pin "4") (pinfunction "A9_4") (pintype "bidirectional"))
      (node (ref "U14") (pin "13") (pinfunction "A9_13") (pintype "bidirectional"))
      (node (ref "U5") (pin "24") (pinfunction "A9_24") (pintype "bidirectional"))
    )
    (net (code "28") (name "Net-(H1-A10)") (class "Default")
      (node (ref "H1") (pin "3") (pinfunction "A10_3") (pintype "bidirectional"))
      (node (ref "U14") (pin "14") (pinfunction "A10_14") (pintype "bidirectional"))
      (node (ref "U5") (pin "21") (pinfunction "A10_21") (pintype "bidirectional"))
    )
    (net (code "29") (name "Net-(H1-A11)") (class "Default")
      (node (ref "H1") (pin "2") (pinfunction "A11_2") (pintype "bidirectional"))
      (node (ref "U14") (pin "15") (pinfunction "A11_15") (pintype "bidirectional"))
    )
    (net (code "30") (name "Net-(H1-A12)") (class "Default")
      (node (ref "H1") (pin "39") (pinfunction "A12_39") (pintype "bidirectional"))
      (node (ref "U14") (pin "16") (pinfunction "A12_16") (pintype "bidirectional"))
    )
    (net (code "31") (name "Net-(H1-A13)") (class "Default")
      (node (ref "H1") (pin "40") (pinfunction "A13_40") (pintype "bidirectional"))
      (node (ref "U14") (pin "17") (pinfunction "A13_17") (pintype "bidirectional"))
      (node (ref "U15") (pin "2") (pinfunction "A1_2") (pintype "bidirectional"))
    )
    (net (code "32") (name "Net-(H1-A14)") (class "Default")
      (node (ref "H1") (pin "41") (pinfunction "A14_41") (pintype "bidirectional"))
      (node (ref "U14") (pin "18") (pinfunction "A14_18") (pintype "bidirectional"))
      (node (ref "U15") (pin "3") (pinfunction "B1_3") (pintype "bidirectional"))
    )
    (net (code "33") (name "Net-(H1-CICCLK)") (class "Default")
      (node (ref "H1") (pin "71") (pinfunction "CICCLK_71") (pintype "bidirectional"))
      (node (ref "R1") (pin "2") (pinfunction "2_2") (pintype "bidirectional"))
      (node (ref "U4") (pin "4") (pinfunction "Y_4") (pintype "bidirectional"))
    )
    (net (code "34") (name "Net-(H1-CICRST)") (class "Default")
      (node (ref "H1") (pin "70") (pinfunction "CICRST_70") (pintype "bidirectional"))
      (node (ref "R1") (pin "1") (pinfunction "1_1") (pintype "bidirectional"))
    )
    (net (code "35") (name "Net-(H1-D0)") (class "Default")
      (node (ref "H1") (pin "49") (pinfunction "D0_49") (pintype "bidirectional"))
      (node (ref "U14") (pin "28") (pinfunction "D0_28") (pintype "bidirectional"))
      (node (ref "U16") (pin "2") (pinfunction "D0_2") (pintype "bidirectional"))
      (node (ref "U17") (pin "18") (pinfunction "1Y1_18") (pintype "bidirectional"))
      (node (ref "U17") (pin "9") (pinfunction "2Y1_9") (pintype "bidirectional"))
      (node (ref "U5") (pin "11") (pinfunction "D0_11") (pintype "bidirectional"))
    )
    (net (code "36") (name "Net-(H1-D1)") (class "Default")
      (node (ref "H1") (pin "48") (pinfunction "D1_48") (pintype "bidirectional"))
      (node (ref "U14") (pin "27") (pinfunction "D1_27") (pintype "bidirectional"))
      (node (ref "U16") (pin "3") (pinfunction "D1_3") (pintype "bidirectional"))
      (node (ref "U17") (pin "12") (pinfunction "1Y4_12") (pintype "bidirectional"))
      (node (ref "U17") (pin "3") (pinfunction "2Y4_3") (pintype "bidirectional"))
      (node (ref "U5") (pin "12") (pinfunction "D1_12") (pintype "bidirectional"))
    )
    (net (code "37") (name "Net-(H1-D2)") (class "Default")
      (node (ref "H1") (pin "47") (pinfunction "D2_47") (pintype "bidirectional"))
      (node (ref "U14") (pin "26") (pinfunction "D2_26") (pintype "bidirectional"))
      (node (ref "U16") (pin "4") (pinfunction "D2_4") (pintype "bidirectional"))
      (node (ref "U5") (pin "13") (pinfunction "D2_13") (pintype "bidirectional"))
    )
    (net (code "38") (name "Net-(H1-D3)") (class "Default")
      (node (ref "H1") (pin "46") (pinfunction "D3_46") (pintype "bidirectional"))
      (node (ref "U14") (pin "25") (pinfunction "D3_25") (pintype "bidirectional"))
      (node (ref "U16") (pin "5") (pinfunction "D3_5") (pintype "bidirectional"))
      (node (ref "U17") (pin "16") (pinfunction "1Y2_16") (pintype "bidirectional"))
      (node (ref "U17") (pin "7") (pinfunction "2Y2_7") (pintype "bidirectional"))
      (node (ref "U5") (pin "15") (pinfunction "D3_15") (pintype "bidirectional"))
    )
    (net (code "39") (name "Net-(H1-D4)") (class "Default")
      (node (ref "H1") (pin "45") (pinfunction "D4_45") (pintype "bidirectional"))
      (node (ref "U14") (pin "24") (pinfunction "D4_24") (pintype "bidirectional"))
      (node (ref "U16") (pin "6") (pinfunction "D4_6") (pintype "bidirectional"))
      (node (ref "U17") (pin "14") (pinfunction "1Y3_14") (pintype "bidirectional"))
      (node (ref "U17") (pin "5") (pinfunction "2Y3_5") (pintype "bidirectional"))
      (node (ref "U5") (pin "16") (pinfunction "D4_16") (pintype "bidirectional"))
    )
    (net (code "40") (name "Net-(H1-D5)") (class "Default")
      (node (ref "H1") (pin "44") (pinfunction "D5_44") (pintype "bidirectional"))
      (node (ref "U14") (pin "23") (pinfunction "D5_23") (pintype "bidirectional"))
      (node (ref "U16") (pin "7") (pinfunction "D5_7") (pintype "bidirectional"))
      (node (ref "U5") (pin "17") (pinfunction "D5_17") (pintype "bidirectional"))
    )
    (net (code "41") (name "Net-(H1-D6)") (class "Default")
      (node (ref "H1") (pin "43") (pinfunction "D6_43") (pintype "bidirectional"))
      (node (ref "U14") (pin "22") (pinfunction "D6_22") (pintype "bidirectional"))
      (node (ref "U16") (pin "8") (pinfunction "D6_8") (pintype "bidirectional"))
      (node (ref "U5") (pin "18") (pinfunction "D6_18") (pintype "bidirectional"))
    )
    (net (code "42") (name "Net-(H1-D7)") (class "Default")
      (node (ref "H1") (pin "42") (pinfunction "D7_42") (pintype "bidirectional"))
      (node (ref "U14") (pin "21") (pinfunction "D7_21") (pintype "bidirectional"))
      (node (ref "U16") (pin "9") (pinfunction "D7_9") (pintype "bidirectional"))
      (node (ref "U5") (pin "19") (pinfunction "D7_19") (pintype "bidirectional"))
    )
    (net (code "43") (name "Net-(H1-EXP6)") (class "Default")
      (node (ref "C16") (pin "1") (pinfunction "1_1") (pintype "bidirectional"))
      (node (ref "H1") (pin "54") (pinfunction "EXP6_54") (pintype "bidirectional"))
    )
    (net (code "44") (name "Net-(H1-M2)") (class "Default")
      (node (ref "H1") (pin "38") (pinfunction "M2_38") (pintype "bidirectional"))
      (node (ref "U14") (pin "31") (pinfunction "M2_31") (pintype "bidirectional"))
      (node (ref "U15") (pin "14") (pinfunction "A2_14") (pintype "bidirectional"))
    )
    (net (code "45") (name "Net-(H1-PA0)") (class "Default")
      (node (ref "H1") (pin "29") (pinfunction "PA0_29") (pintype "bidirectional"))
      (node (ref "U13") (pin "19") (pinfunction "8Q_19") (pintype "bidirectional"))
      (node (ref "U6") (pin "10") (pinfunction "A0_10") (pintype "bidirectional"))
    )
    (net (code "46") (name "Net-(H1-PA1)") (class "Default")
      (node (ref "H1") (pin "28") (pinfunction "PA1_28") (pintype "bidirectional"))
      (node (ref "U13") (pin "16") (pinfunction "7Q_16") (pintype "bidirectional"))
      (node (ref "U6") (pin "9") (pinfunction "A1_9") (pintype "bidirectional"))
    )
    (net (code "47") (name "Net-(H1-PA2)") (class "Default")
      (node (ref "H1") (pin "27") (pinfunction "PA2_27") (pintype "bidirectional"))
      (node (ref "U13") (pin "15") (pinfunction "6Q_15") (pintype "bidirectional"))
      (node (ref "U6") (pin "8") (pinfunction "A2_8") (pintype "bidirectional"))
    )
    (net (code "48") (name "Net-(H1-PA3)") (class "Default")
      (node (ref "H1") (pin "26") (pinfunction "PA3_26") (pintype "bidirectional"))
      (node (ref "U13") (pin "12") (pinfunction "5Q_12") (pintype "bidirectional"))
      (node (ref "U6") (pin "7") (pinfunction "A3_7") (pintype "bidirectional"))
    )
    (net (code "49") (name "Net-(H1-PA4)") (class "Default")
      (node (ref "H1") (pin "25") (pinfunction "PA4_25") (pintype "bidirectional"))
      (node (ref "U13") (pin "9") (pinfunction "4Q_9") (pintype "bidirectional"))
      (node (ref "U6") (pin "6") (pinfunction "A4_6") (pintype "bidirectional"))
    )
    (net (code "50") (name "Net-(H1-PA5)") (class "Default")
      (node (ref "H1") (pin "24") (pinfunction "PA5_24") (pintype "bidirectional"))
      (node (ref "U13") (pin "6") (pinfunction "3Q_6") (pintype "bidirectional"))
      (node (ref "U6") (pin "5") (pinfunction "A5_5") (pintype "bidirectional"))
    )
    (net (code "51") (name "Net-(H1-PA6)") (class "Default")
      (node (ref "H1") (pin "23") (pinfunction "PA6_23") (pintype "bidirectional"))
      (node (ref "U13") (pin "5") (pinfunction "2Q_5") (pintype "bidirectional"))
      (node (ref "U6") (pin "4") (pinfunction "A6_4") (pintype "bidirectional"))
    )
    (net (code "52") (name "Net-(H1-PA7)") (class "Default")
      (node (ref "H1") (pin "59") (pinfunction "PA7_59") (pintype "bidirectional"))
      (node (ref "U13") (pin "2") (pinfunction "1Q_2") (pintype "bidirectional"))
      (node (ref "U6") (pin "3") (pinfunction "A7_3") (pintype "bidirectional"))
    )
    (net (code "53") (name "Net-(H1-PA8)") (class "Default")
      (node (ref "H1") (pin "60") (pinfunction "PA8_60") (pintype "bidirectional"))
      (node (ref "U16") (pin "30") (pinfunction "PA8_30") (pintype "bidirectional"))
      (node (ref "U6") (pin "25") (pinfunction "A8_25") (pintype "bidirectional"))
    )
    (net (code "54") (name "Net-(H1-PA9)") (class "Default")
      (node (ref "H1") (pin "61") (pinfunction "PA9_61") (pintype "bidirectional"))
      (node (ref "U16") (pin "29") (pinfunction "PA9_29") (pintype "bidirectional"))
      (node (ref "U6") (pin "24") (pinfunction "A9_24") (pintype "bidirectional"))
    )
    (net (code "55") (name "Net-(H1-PA10)") (class "Default")
      (node (ref "H1") (pin "63") (pinfunction "PA10_63") (pintype "bidirectional"))
      (node (ref "U16") (pin "28") (pinfunction "PA10_28") (pintype "bidirectional"))
    )
    (net (code "56") (name "Net-(H1-PA11)") (class "Default")
      (node (ref "H1") (pin "62") (pinfunction "PA11_62") (pintype "bidirectional"))
      (node (ref "U16") (pin "27") (pinfunction "PA11_27") (pintype "bidirectional"))
    )
    (net (code "57") (name "Net-(H1-PA12)") (class "Default")
      (node (ref "H1") (pin "64") (pinfunction "PA12_64") (pintype "bidirectional"))
      (node (ref "U16") (pin "26") (pinfunction "PA12_26") (pintype "bidirectional"))
    )
    (net (code "58") (name "Net-(H1-PA13)") (class "Default")
      (node (ref "H1") (pin "65") (pinfunction "PA13_65") (pintype "bidirectional"))
      (node (ref "R2") (pin "1") (pinfunction "1_1") (pintype "bidirectional"))
      (node (ref "U1") (pin "2") (pinfunction "A_2") (pintype "bidirectional"))
      (node (ref "U16") (pin "25") (pinfunction "PA13_25") (pintype "bidirectional"))
    )
    (net (code "59") (name "Net-(H1-PD0)") (class "Default")
      (node (ref "H1") (pin "30") (pinfunction "PD0_30") (pintype "bidirectional"))
      (node (ref "U13") (pin "18") (pinfunction "8D_18") (pintype "bidirectional"))
      (node (ref "U16") (pin "38") (pinfunction "PD0_38") (pintype "bidirectional"))
      (node (ref "U6") (pin "11") (pinfunction "D0_11") (pintype "bidirectional"))
    )
    (net (code "60") (name "Net-(H1-PD1)") (class "Default")
      (node (ref "H1") (pin "31") (pinfunction "PD1_31") (pintype "bidirectional"))
      (node (ref "U13") (pin "17") (pinfunction "7D_17") (pintype "bidirectional"))
      (node (ref "U16") (pin "37") (pinfunction "PD1_37") (pintype "bidirectional"))
      (node (ref "U6") (pin "12") (pinfunction "D1_12") (pintype "bidirectional"))
    )
    (net (code "61") (name "Net-(H1-PD2)") (class "Default")
      (node (ref "H1") (pin "32") (pinfunction "PD2_32") (pintype "bidirectional"))
      (node (ref "U13") (pin "14") (pinfunction "6D_14") (pintype "bidirectional"))
      (node (ref "U16") (pin "36") (pinfunction "PD2_36") (pintype "bidirectional"))
      (node (ref "U6") (pin "13") (pinfunction "D2_13") (pintype "bidirectional"))
    )
    (net (code "62") (name "Net-(H1-PD3)") (class "Default")
      (node (ref "H1") (pin "33") (pinfunction "PD3_33") (pintype "bidirectional"))
      (node (ref "U13") (pin "13") (pinfunction "5D_13") (pintype "bidirectional"))
      (node (ref "U16") (pin "35") (pinfunction "PD3_35") (pintype "bidirectional"))
      (node (ref "U6") (pin "15") (pinfunction "D3_15") (pintype "bidirectional"))
    )
    (net (code "63") (name "Net-(H1-PD4)") (class "Default")
      (node (ref "H1") (pin "69") (pinfunction "PD4_69") (pintype "bidirectional"))
      (node (ref "U13") (pin "8") (pinfunction "4D_8") (pintype "bidirectional"))
      (node (ref "U16") (pin "34") (pinfunction "PD4_34") (pintype "bidirectional"))
      (node (ref "U6") (pin "16") (pinfunction "D4_16") (pintype "bidirectional"))
    )
    (net (code "64") (name "Net-(H1-PD5)") (class "Default")
      (node (ref "H1") (pin "68") (pinfunction "PD5_68") (pintype "bidirectional"))
      (node (ref "U13") (pin "7") (pinfunction "3D_7") (pintype "bidirectional"))
      (node (ref "U16") (pin "33") (pinfunction "PD5_33") (pintype "bidirectional"))
      (node (ref "U6") (pin "17") (pinfunction "D5_17") (pintype "bidirectional"))
    )
    (net (code "65") (name "Net-(H1-PD6)") (class "Default")
      (node (ref "H1") (pin "67") (pinfunction "PD6_67") (pintype "bidirectional"))
      (node (ref "U13") (pin "4") (pinfunction "2D_4") (pintype "bidirectional"))
      (node (ref "U16") (pin "32") (pinfunction "PD6_32") (pintype "bidirectional"))
      (node (ref "U6") (pin "18") (pinfunction "D6_18") (pintype "bidirectional"))
    )
    (net (code "66") (name "Net-(H1-PD7)") (class "Default")
      (node (ref "H1") (pin "66") (pinfunction "PD7_66") (pintype "bidirectional"))
      (node (ref "U13") (pin "3") (pinfunction "1D_3") (pintype "bidirectional"))
      (node (ref "U16") (pin "31") (pinfunction "PD7_31") (pintype "bidirectional"))
      (node (ref "U6") (pin "19") (pinfunction "D7_19") (pintype "bidirectional"))
    )
    (net (code "67") (name "Net-(H1-R{slash}~{W})") (class "Default")
      (node (ref "H1") (pin "14") (pinfunction "R/~{W}_14") (pintype "bidirectional"))
      (node (ref "U14") (pin "34") (pinfunction "R/~{W}_34") (pintype "bidirectional"))
      (node (ref "U16") (pin "1") (pinfunction "R/~{W}_1") (pintype "bidirectional"))
      (node (ref "U5") (pin "27") (pinfunction "~{WE}_27") (pintype "bidirectional"))
    )
    (net (code "68") (name "Net-(H1-SCLK)") (class "Default")
      (node (ref "H1") (pin "37") (pinfunction "SCLK_37") (pintype "bidirectional"))
      (node (ref "R3") (pin "1") (pinfunction "1_1") (pintype "bidirectional"))
    )
    (net (code "69") (name "Net-(H1-VA10)") (class "Default")
      (node (ref "H1") (pin "22") (pinfunction "VA10_22") (pintype "bidirectional"))
      (node (ref "U6") (pin "21") (pinfunction "A10_21") (pintype "bidirectional"))
    )
    (net (code "70") (name "Net-(H1-~{CS})") (class "Default")
      (node (ref "H1") (pin "57") (pinfunction "~{CS}_57") (pintype "bidirectional"))
      (node (ref "U6") (pin "20") (pinfunction "~{CE}_20") (pintype "bidirectional"))
    )
    (net (code "71") (name "Net-(H1-~{IRQ})") (class "Default")
      (node (ref "H1") (pin "15") (pinfunction "~{IRQ}_15") (pintype "bidirectional"))
      (node (ref "R15") (pin "1") (pinfunction "1_1") (pintype "bidirectional"))
      (node (ref "U14") (pin "32") (pinfunction "~{IRQ}_32") (pintype "bidirectional"))
    )
    (net (code "72") (name "Net-(H1-~{PA13})") (class "Default")
      (node (ref "H1") (pin "58") (pinfunction "~{PA13}_58") (pintype "bidirectional"))
      (node (ref "U1") (pin "4") (pinfunction "Y_4") (pintype "bidirectional"))
    )
    (net (code "73") (name "Net-(H1-~{RD})") (class "Default")
      (node (ref "C25") (pin "2") (pinfunction "2_2") (pintype "bidirectional"))
      (node (ref "H1") (pin "21") (pinfunction "~{RD}_21") (pintype "bidirectional"))
      (node (ref "U16") (pin "24") (pinfunction "~{RD}_24") (pintype "bidirectional"))
      (node (ref "U6") (pin "22") (pinfunction "~{OE}_22") (pintype "bidirectional"))
    )
    (net (code "74") (name "Net-(H1-~{ROMSL})") (class "Default")
      (node (ref "H1") (pin "50") (pinfunction "~{ROMSL}_50") (pintype "bidirectional"))
      (node (ref "U15") (pin "9") (pinfunction "2Y3_9") (pintype "bidirectional"))
    )
    (net (code "75") (name "Net-(H1-~{WR})") (class "Default")
      (node (ref "H1") (pin "56") (pinfunction "~{WR}_56") (pintype "bidirectional"))
      (node (ref "U16") (pin "23") (pinfunction "~{WR}_23") (pintype "bidirectional"))
      (node (ref "U6") (pin "27") (pinfunction "~{WE}_27") (pintype "bidirectional"))
    )
    (net (code "76") (name "Net-(J2-T-Pad2B)") (class "Default")
      (node (ref "J2") (pin "2B") (pinfunction "T_2B") (pintype "bidirectional"))
      (node (ref "J2") (pin "2T") (pinfunction "T_2T") (pintype "bidirectional"))
      (node (ref "R22") (pin "2") (pinfunction "2_2") (pintype "bidirectional"))
    )
    (net (code "77") (name "Net-(J3-RS)") (class "Default")
      (node (ref "C27") (pin "2") (pinfunction "2_2") (pintype "bidirectional"))
      (node (ref "J3") (pin "4") (pinfunction "RS_4") (pintype "bidirectional"))
    )
    (net (code "78") (name "Net-(J3-RT)") (class "Default")
      (node (ref "C28") (pin "2") (pinfunction "2_2") (pintype "bidirectional"))
      (node (ref "J3") (pin "3") (pinfunction "RT_3") (pintype "bidirectional"))
    )
    (net (code "79") (name "Net-(J3-T)") (class "Default")
      (node (ref "C29") (pin "2") (pinfunction "2_2") (pintype "bidirectional"))
      (node (ref "J3") (pin "2") (pinfunction "T_2") (pintype "bidirectional"))
    )
    (net (code "80") (name "Net-(J4-CC1)") (class "Default")
      (node (ref "J4") (pin "A5") (pinfunction "CC1_A5") (pintype "bidirectional"))
      (node (ref "R23") (pin "2") (pinfunction "2_2") (pintype "bidirectional"))
    )
    (net (code "81") (name "Net-(J4-CC2)") (class "Default")
      (node (ref "J4") (pin "B5") (pinfunction "CC2_B5") (pintype "bidirectional"))
      (node (ref "R24") (pin "2") (pinfunction "2_2") (pintype "bidirectional"))
    )
    (net (code "82") (name "Net-(P1-CW)") (class "Default")
      (node (ref "C27") (pin "1") (pinfunction "1_1") (pintype "bidirectional"))
      (node (ref "P1") (pin "3") (pinfunction "CW_3") (pintype "passive"))
      (node (ref "R12") (pin "2") (pinfunction "2_2") (pintype "bidirectional"))
      (node (ref "U12") (pin "12") (pinfunction "OUT_12") (pintype "output"))
    )
    (net (code "83") (name "Net-(P1-WIPER)") (class "Default")
      (node (ref "P1") (pin "2") (pinfunction "WIPER_2") (pintype "passive"))
      (node (ref "R11") (pin "1") (pinfunction "1_1") (pintype "bidirectional"))
    )
    (net (code "84") (name "Net-(Q1-B)") (class "Default")
      (node (ref "Q1") (pin "1") (pinfunction "B_1") (pintype "bidirectional"))
      (node (ref "U16") (pin "21") (pinfunction "VIDEO_21") (pintype "bidirectional"))
    )
    (net (code "85") (name "Net-(Q1-E)") (class "Default")
      (node (ref "C31") (pin "A") (pinfunction "A_A") (pintype "bidirectional"))
      (node (ref "Q1") (pin "2") (pinfunction "E_2") (pintype "bidirectional"))
      (node (ref "R19") (pin "2") (pinfunction "2_2") (pintype "bidirectional"))
    )
    (net (code "86") (name "Net-(RGB-EX3)") (class "Default")
      (node (ref "R25") (pin "2") (pinfunction "2_2") (pintype "bidirectional"))
      (node (ref "RGB") (pin "EXT3") (pinfunction "EX3_EXT3") (pintype "bidirectional"))
      (node (ref "U16") (pin "17") (pinfunction "EXT3_17") (pintype "bidirectional"))
    )
    (net (code "87") (name "Net-(S1-1)") (class "Default")
      (node (ref "S1") (pin "BA") (pinfunction "1_BA") (pintype "bidirectional"))
      (node (ref "U2") (pin "4") (pinfunction "VDD_4") (pintype "bidirectional"))
    )
    (net (code "88") (name "Net-(S1-2)") (class "Default")
      (node (ref "C1") (pin "1") (pinfunction "1_1") (pintype "bidirectional"))
      (node (ref "C6") (pin "1") (pinfunction "1_1") (pintype "bidirectional"))
      (node (ref "C8") (pin "1") (pinfunction "1_1") (pintype "bidirectional"))
      (node (ref "S1") (pin "BCOM") (pinfunction "2_BCOM") (pintype "bidirectional"))
      (node (ref "U7") (pin "5") (pinfunction "VDD_5") (pintype "bidirectional"))
      (node (ref "U9") (pin "2") (pinfunction "VOUT_2") (pintype "bidirectional"))
    )
    (net (code "89") (name "Net-(S1-3)") (class "Default")
      (node (ref "S1") (pin "BB") (pinfunction "3_BB") (pintype "bidirectional"))
      (node (ref "U8") (pin "4") (pinfunction "VDD_4") (pintype "bidirectional"))
    )
    (net (code "90") (name "Net-(S1-4)") (class "Default")
      (node (ref "S1") (pin "AA") (pinfunction "4_AA") (pintype "bidirectional"))
      (node (ref "U2") (pin "5") (pinfunction "OUT_5") (pintype "bidirectional"))
    )
    (net (code "91") (name "Net-(S1-5)") (class "Default")
      (node (ref "S1") (pin "ACOM") (pinfunction "5_ACOM") (pintype "bidirectional"))
      (node (ref "U7") (pin "3") (pinfunction "FIN_3") (pintype "bidirectional"))
    )
    (net (code "92") (name "Net-(S1-6)") (class "Default")
      (node (ref "S1") (pin "AB") (pinfunction "6_AB") (pintype "bidirectional"))
      (node (ref "U8") (pin "5") (pinfunction "OUT_5") (pintype "bidirectional"))
    )
    (net (code "93") (name "Net-(S2-1)") (class "Default")
      (node (ref "S2") (pin "BA") (pinfunction "1_BA") (pintype "bidirectional"))
      (node (ref "U11") (pin "5") (pinfunction "Q_5") (pintype "bidirectional"))
      (node (ref "U14") (pin "29") (pinfunction "CLK_29") (pintype "bidirectional"))
    )
    (net (code "94") (name "Net-(S2-2)") (class "Default")
      (node (ref "R4") (pin "1") (pinfunction "1_1") (pintype "bidirectional"))
      (node (ref "S2") (pin "BCOM") (pinfunction "2_BCOM") (pintype "bidirectional"))
    )
    (net (code "95") (name "Net-(S2-3)") (class "Default")
      (node (ref "S2") (pin "BB") (pinfunction "3_BB") (pintype "bidirectional"))
      (node (ref "U3") (pin "1") (pinfunction "X1_1") (pintype "bidirectional"))
    )
    (net (code "96") (name "Net-(S2-5)") (class "Default")
      (node (ref "C4") (pin "2") (pinfunction "2_2") (pintype "bidirectional"))
      (node (ref "C7") (pin "1") (pinfunction "1_1") (pintype "bidirectional"))
      (node (ref "C9") (pin "1") (pinfunction "1_1") (pintype "bidirectional"))
      (node (ref "S2") (pin "ACOM") (pinfunction "5_ACOM") (pintype "bidirectional"))
      (node (ref "U10") (pin "6") (pinfunction "~{R}D_6") (pintype "bidirectional"))
      (node (ref "U10") (pin "7") (pinfunction "~{S}D_7") (pintype "bidirectional"))
      (node (ref "U10") (pin "8") (pinfunction "VCC_8") (pintype "bidirectional"))
      (node (ref "U11") (pin "6") (pinfunction "~{R}D_6") (pintype "bidirectional"))
      (node (ref "U11") (pin "7") (pinfunction "~{S}D_7") (pintype "bidirectional"))
      (node (ref "U11") (pin "8") (pinfunction "VCC_8") (pintype "bidirectional"))
      (node (ref "U3") (pin "2") (pinfunction "VDD_2") (pintype "bidirectional"))
      (node (ref "U3") (pin "6") (pinfunction "S0_6") (pintype "bidirectional"))
      (node (ref "U3") (pin "7") (pinfunction "OE_7") (pintype "bidirectional"))
    )
    (net (code "97") (name "Net-(U7-CLK0)") (class "Default")
      (node (ref "R4") (pin "2") (pinfunction "2_2") (pintype "bidirectional"))
      (node (ref "U7") (pin "4") (pinfunction "CLK0_4") (pintype "bidirectional"))
    )
    (net (code "98") (name "Net-(U7-CLK1)") (class "Default")
      (node (ref "R5") (pin "2") (pinfunction "2_2") (pintype "bidirectional"))
      (node (ref "U7") (pin "1") (pinfunction "CLK1_1") (pintype "bidirectional"))
    )
    (net (code "99") (name "Net-(U7-CLK2)") (class "Default")
      (node (ref "R3") (pin "2") (pinfunction "2_2") (pintype "bidirectional"))
      (node (ref "U7") (pin "6") (pinfunction "CLK2_6") (pintype "bidirectional"))
    )
    (net (code "100") (name "Net-(U10-CP)") (class "Default")
      (node (ref "U10") (pin "1") (pinfunction "CP_1") (pintype "bidirectional"))
      (node (ref "U3") (pin "5") (pinfunction "CLK_5") (pintype "bidirectional"))
    )
    (net (code "101") (name "Net-(U10-D)") (class "Default")
      (node (ref "U10") (pin "2") (pinfunction "D_2") (pintype "bidirectional"))
      (node (ref "U10") (pin "3") (pinfunction "~{Q}_3") (pintype "bidirectional"))
    )
    (net (code "102") (name "Net-(U10-Q)") (class "Default")
      (node (ref "U10") (pin "5") (pinfunction "Q_5") (pintype "bidirectional"))
      (node (ref "U11") (pin "1") (pinfunction "CP_1") (pintype "bidirectional"))
    )
    (net (code "103") (name "Net-(U11-D)") (class "Default")
      (node (ref "U11") (pin "2") (pinfunction "D_2") (pintype "bidirectional"))
      (node (ref "U11") (pin "3") (pinfunction "~{Q}_3") (pintype "bidirectional"))
    )
    (net (code "104") (name "Net-(U12A--)") (class "Default")
      (node (ref "R10") (pin "2") (pinfunction "2_2") (pintype "bidirectional"))
      (node (ref "R14") (pin "1") (pinfunction "1_1") (pintype "bidirectional"))
      (node (ref "U12") (pin "2") (pinfunction "-_2") (pintype "input"))
    )
    (net (code "105") (name "Net-(U12A-OUT)") (class "Default")
      (node (ref "R14") (pin "2") (pinfunction "2_2") (pintype "bidirectional"))
      (node (ref "R22") (pin "1") (pinfunction "1_1") (pintype "bidirectional"))
      (node (ref "U12") (pin "3") (pinfunction "OUT_3") (pintype "output"))
    )
    (net (code "106") (name "Net-(U12B--)") (class "Default")
      (node (ref "R12") (pin "1") (pinfunction "1_1") (pintype "bidirectional"))
      (node (ref "R13") (pin "2") (pinfunction "2_2") (pintype "bidirectional"))
      (node (ref "U12") (pin "13") (pinfunction "-_13") (pintype "input"))
    )
    (net (code "107") (name "Net-(U12C-CN)") (class "Default")
      (node (ref "C11") (pin "1") (pinfunction "1_1") (pintype "bidirectional"))
      (node (ref "U12") (pin "7") (pinfunction "CN_7") (pintype "bidirectional"))
    )
    (net (code "108") (name "Net-(U12C-CP)") (class "Default")
      (node (ref "C11") (pin "2") (pinfunction "2_2") (pintype "bidirectional"))
      (node (ref "U12") (pin "8") (pinfunction "CP_8") (pintype "bidirectional"))
    )
    (net (code "109") (name "Net-(U12C-VSS)") (class "Default")
      (node (ref "C12") (pin "2") (pinfunction "2_2") (pintype "bidirectional"))
      (node (ref "U12") (pin "6") (pinfunction "VSS_6") (pintype "bidirectional"))
    )
    (net (code "110") (name "Net-(U13-C)") (class "Default")
      (node (ref "U13") (pin "11") (pinfunction "C_11") (pintype "bidirectional"))
      (node (ref "U16") (pin "39") (pinfunction "ALE_39") (pintype "bidirectional"))
    )
    (net (code "111") (name "Net-(U14-A15)") (class "Default")
      (node (ref "U14") (pin "19") (pinfunction "A15_19") (pintype "bidirectional"))
      (node (ref "U15") (pin "13") (pinfunction "B2_13") (pintype "bidirectional"))
    )
    (net (code "112") (name "Net-(U14-AUD1)") (class "Default")
      (node (ref "C29") (pin "1") (pinfunction "1_1") (pintype "bidirectional"))
      (node (ref "R8") (pin "1") (pinfunction "1_1") (pintype "bidirectional"))
      (node (ref "R9") (pin "2") (pinfunction "2_2") (pintype "bidirectional"))
      (node (ref "U14") (pin "1") (pinfunction "AUD1_1") (pintype "bidirectional"))
    )
    (net (code "113") (name "Net-(U14-AUD2)") (class "Default")
      (node (ref "C28") (pin "1") (pinfunction "1_1") (pintype "bidirectional"))
      (node (ref "R6") (pin "1") (pinfunction "1_1") (pintype "bidirectional"))
      (node (ref "R7") (pin "2") (pinfunction "2_2") (pintype "bidirectional"))
      (node (ref "U14") (pin "2") (pinfunction "AUD2_2") (pintype "bidirectional"))
    )
    (net (code "114") (name "Net-(U14-~{NMI})") (class "Default")
      (node (ref "R17") (pin "1") (pinfunction "1_1") (pintype "bidirectional"))
      (node (ref "U14") (pin "33") (pinfunction "~{NMI}_33") (pintype "bidirectional"))
      (node (ref "U16") (pin "19") (pinfunction "~{INT}_19") (pintype "bidirectional"))
    )
    (net (code "115") (name "Net-(U14-~{RST})") (class "Default")
      (node (ref "U14") (pin "3") (pinfunction "~{RST}_3") (pintype "bidirectional"))
      (node (ref "U16") (pin "22") (pinfunction "~{RST}_22") (pintype "bidirectional"))
      (node (ref "U18") (pin "2") (pinfunction "A_2") (pintype "bidirectional"))
      (node (ref "U19") (pin "2") (pinfunction "~{RST}_2") (pintype "bidirectional"))
      (node (ref "U4") (pin "2") (pinfunction "A_2") (pintype "bidirectional"))
    )
    (net (code "116") (name "Net-(U15-1Y0)") (class "Default")
      (node (ref "U15") (pin "4") (pinfunction "1Y0_4") (pintype "bidirectional"))
      (node (ref "U5") (pin "20") (pinfunction "~{CE}_20") (pintype "bidirectional"))
    )
    (net (code "117") (name "Net-(U15-1Y1)") (class "Default")
      (node (ref "U15") (pin "5") (pinfunction "1Y1_5") (pintype "bidirectional"))
      (node (ref "U16") (pin "13") (pinfunction "~{CS}_13") (pintype "bidirectional"))
    )
    (net (code "118") (name "Net-(U15-2Y1)") (class "Default")
      (node (ref "U15") (pin "1") (pinfunction "G1_1") (pintype "bidirectional"))
      (node (ref "U15") (pin "11") (pinfunction "2Y1_11") (pintype "bidirectional"))
    )
    (net (code "119") (name "Net-(U16-A0)") (class "Default")
      (node (ref "S5") (pin "2") (pinfunction "2_2") (pintype "bidirectional"))
      (node (ref "U16") (pin "12") (pinfunction "A0_12") (pintype "bidirectional"))
    )
    (net (code "120") (name "Net-(U16-CLK)") (class "Default")
      (node (ref "R5") (pin "1") (pinfunction "1_1") (pintype "bidirectional"))
      (node (ref "U16") (pin "18") (pinfunction "CLK_18") (pintype "bidirectional"))
    )
    (net (code "121") (name "Net-(U16-EXT0)") (class "Default")
      (node (ref "R28") (pin "2") (pinfunction "2_2") (pintype "bidirectional"))
      (node (ref "RGB") (pin "R") (pinfunction "R_R") (pintype "bidirectional"))
      (node (ref "U16") (pin "14") (pinfunction "EXT0_14") (pintype "bidirectional"))
    )
    (net (code "122") (name "Net-(U16-EXT1)") (class "Default")
      (node (ref "R27") (pin "2") (pinfunction "2_2") (pintype "bidirectional"))
      (node (ref "RGB") (pin "G") (pinfunction "G_G") (pintype "bidirectional"))
      (node (ref "U16") (pin "15") (pinfunction "EXT1_15") (pintype "bidirectional"))
    )
    (net (code "123") (name "Net-(U16-EXT2)") (class "Default")
      (node (ref "R26") (pin "2") (pinfunction "2_2") (pintype "bidirectional"))
      (node (ref "RGB") (pin "B") (pinfunction "B_B") (pintype "bidirectional"))
      (node (ref "U16") (pin "16") (pinfunction "EXT2_16") (pintype "bidirectional"))
    )
    (net (code "124") (name "Net-(U17-1A4)") (class "Default")
      (node (ref "R16") (pin "1") (pinfunction "1_1") (pintype "bidirectional"))
      (node (ref "U17") (pin "17") (pinfunction "2A4_17") (pintype "bidirectional"))
      (node (ref "U17") (pin "8") (pinfunction "1A4_8") (pintype "bidirectional"))
    )
    (net (code "125") (name "Net-(U19-~{MR})") (class "Default")
      (node (ref "S3") (pin "1") (pinfunction "1_1") (pintype "bidirectional"))
      (node (ref "U19") (pin "3") (pinfunction "~{MR}_3") (pintype "bidirectional"))
    )
    (net (code "126") (name "Net-(U20-ON)") (class "Default")
      (node (ref "S4") (pin "2") (pinfunction "2_2") (pintype "bidirectional"))
      (node (ref "U20") (pin "3") (pinfunction "ON_3") (pintype "bidirectional"))
    )
    (net (code "127") (name "Net-(U20-VIN)") (class "Default")
      (node (ref "C32") (pin "A") (pinfunction "A_A") (pintype "bidirectional"))
      (node (ref "C36") (pin "2") (pinfunction "2_2") (pintype "bidirectional"))
      (node (ref "J4") (pin "A9") (pinfunction "VBUS_A9") (pintype "bidirectional"))
      (node (ref "J4") (pin "B9") (pinfunction "VBUS_B9") (pintype "bidirectional"))
      (node (ref "S4") (pin "1") (pinfunction "1_1") (pintype "bidirectional"))
      (node (ref "U20") (pin "1") (pinfunction "VIN_1") (pintype "bidirectional"))
    )
    (net (code "128") (name "Net-(U21-Y)") (class "Default")
      (node (ref "U21") (pin "4") (pinfunction "Y_4") (pintype "output"))
      (node (ref "U22") (pin "2") (pinfunction "A_2") (pintype "input"))
    )
    (net (code "129") (name "Net-(U22-Y)") (class "Default")
      (node (ref "S5") (pin "3") (pinfunction "3_3") (pintype "bidirectional"))
      (node (ref "U22") (pin "4") (pinfunction "Y_4") (pintype "output"))
    )
    (net (code "130") (name "VCC") (class "Default")
      (node (ref "C13") (pin "2") (pinfunction "2_2") (pintype "bidirectional"))
      (node (ref "C14") (pin "1") (pinfunction "1_1") (pintype "bidirectional"))
      (node (ref "C15") (pin "A") (pinfunction "A_A") (pintype "bidirectional"))
      (node (ref "C17") (pin "1") (pinfunction "1_1") (pintype "bidirectional"))
      (node (ref "C18") (pin "1") (pinfunction "1_1") (pintype "bidirectional"))
      (node (ref "C2") (pin "1") (pinfunction "1_1") (pintype "bidirectional"))
      (node (ref "C22") (pin "P") (pinfunction "A_P") (pintype "bidirectional"))
      (node (ref "C24") (pin "1") (pinfunction "1_1") (pintype "bidirectional"))
      (node (ref "C3") (pin "1") (pinfunction "1_1") (pintype "bidirectional"))
      (node (ref "C33") (pin "1") (pinfunction "1_1") (pintype "bidirectional"))
      (node (ref "C38") (pin "2") (pinfunction "2_2") (pintype "bidirectional"))
      (node (ref "C5") (pin "1") (pinfunction "1_1") (pintype "bidirectional"))
      (node (ref "DA2") (pin "3") (pinfunction "COM_3") (pintype "bidirectional"))
      (node (ref "DA2") (pin "6") (pinfunction "COM_6") (pintype "bidirectional"))
      (node (ref "DA4") (pin "3") (pinfunction "COM_3") (pintype "bidirectional"))
      (node (ref "DA4") (pin "6") (pinfunction "COM_6") (pintype "bidirectional"))
      (node (ref "DA5") (pin "2") (pinfunction "K_2") (pintype "bidirectional"))
      (node (ref "H1") (pin "36") (pinfunction "VCC_36") (pintype "bidirectional"))
      (node (ref "H5") (pin "5") (pinfunction "VCC_5") (pintype "bidirectional"))
      (node (ref "H6") (pin "5") (pinfunction "VCC_5") (pintype "bidirectional"))
      (node (ref "R15") (pin "2") (pinfunction "2_2") (pintype "bidirectional"))
      (node (ref "R16") (pin "2") (pinfunction "2_2") (pintype "bidirectional"))
      (node (ref "R17") (pin "2") (pinfunction "2_2") (pintype "bidirectional"))
      (node (ref "R18") (pin "2") (pinfunction "2_2") (pintype "bidirectional"))
      (node (ref "R19") (pin "1") (pinfunction "1_1") (pintype "bidirectional"))
      (node (ref "R2") (pin "2") (pinfunction "2_2") (pintype "bidirectional"))
      (node (ref "R20") (pin "2") (pinfunction "2_2") (pintype "bidirectional"))
      (node (ref "RA1") (pin "10") (pinfunction "COM_10") (pintype "bidirectional"))
      (node (ref "RA1") (pin "5") (pinfunction "COM_5") (pintype "bidirectional"))
      (node (ref "RGB") (pin "VCC@1") (pinfunction "VCC_VCC@1") (pintype "bidirectional"))
      (node (ref "RGB") (pin "VCC@2") (pinfunction "VCC_VCC@2") (pintype "bidirectional"))
      (node (ref "RGB") (pin "VCC@3") (pinfunction "VCC_VCC@3") (pintype "bidirectional"))
      (node (ref "S2") (pin "AB") (pinfunction "6_AB") (pintype "bidirectional"))
      (node (ref "U1") (pin "5") (pinfunction "VCC_5") (pintype "bidirectional"))
      (node (ref "U12") (pin "11") (pinfunction "UVP_11") (pintype "bidirectional"))
      (node (ref "U12") (pin "5") (pinfunction "EN_5") (pintype "bidirectional"))
      (node (ref "U12") (pin "9") (pinfunction "VDD_9") (pintype "bidirectional"))
      (node (ref "U13") (pin "20") (pinfunction "VCC_20") (pintype "bidirectional"))
      (node (ref "U14") (pin "40") (pinfunction "VCC_40") (pintype "bidirectional"))
      (node (ref "U15") (pin "16") (pinfunction "VCC_16") (pintype "bidirectional"))
      (node (ref "U16") (pin "40") (pinfunction "VCC_40") (pintype "bidirectional"))
      (node (ref "U17") (pin "20") (pinfunction "VCC_20") (pintype "bidirectional"))
      (node (ref "U18") (pin "5") (pinfunction "VCC_5") (pintype "bidirectional"))
      (node (ref "U19") (pin "4") (pinfunction "VCC_4") (pintype "bidirectional"))
      (node (ref "U20") (pin "5") (pinfunction "VOUT_5") (pintype "bidirectional"))
      (node (ref "U21") (pin "5") (pinfunction "VCC_5") (pintype "power_in"))
      (node (ref "U22") (pin "5") (pinfunction "VCC_5") (pintype "power_in"))
      (node (ref "U4") (pin "5") (pinfunction "VCC_5") (pintype "bidirectional"))
      (node (ref "U5") (pin "28") (pinfunction "VCC_28") (pintype "bidirectional"))
      (node (ref "U6") (pin "28") (pinfunction "VCC_28") (pintype "bidirectional"))
      (node (ref "U9") (pin "3") (pinfunction "VIN_3") (pintype "bidirectional"))
    )
    (net (code "131") (name "unconnected-(P1-CCW-Pad1)") (class "Default")
      (node (ref "P1") (pin "1") (pinfunction "CCW_1") (pintype "passive"))
    )
    (net (code "132") (name "unconnected-(U3-X2-Pad8)") (class "Default")
      (node (ref "U3") (pin "8") (pinfunction "X2_8") (pintype "bidirectional"))
    )
    (net (code "133") (name "unconnected-(U14-OUT1-Pad38)") (class "Default")
      (node (ref "U14") (pin "38") (pinfunction "OUT1_38") (pintype "bidirectional"))
    )
    (net (code "134") (name "unconnected-(U14-OUT2-Pad37)") (class "Default")
      (node (ref "U14") (pin "37") (pinfunction "OUT2_37") (pintype "bidirectional"))
    )
    (net (code "135") (name "unconnected-(U15-1Y2-Pad6)") (class "Default")
      (node (ref "U15") (pin "6") (pinfunction "1Y2_6") (pintype "bidirectional"))
    )
    (net (code "136") (name "unconnected-(U15-1Y3-Pad7)") (class "Default")
      (node (ref "U15") (pin "7") (pinfunction "1Y3_7") (pintype "bidirectional"))
    )
    (net (code "137") (name "unconnected-(U15-2Y0-Pad12)") (class "Default")
      (node (ref "U15") (pin "12") (pinfunction "2Y0_12") (pintype "bidirectional"))
    )
    (net (code "138") (name "unconnected-(U15-2Y2-Pad10)") (class "Default")
      (node (ref "U15") (pin "10") (pinfunction "2Y2_10") (pintype "bidirectional"))
    )
    (net (code "139") (name "unconnected-(U20-FLAGB-Pad4)") (class "Default")
      (node (ref "U20") (pin "4") (pinfunction "FLAGB_4") (pintype "bidirectional"))
    )
  )
)
